# RX08-3-5-9.net
KiCad netlist of a schematic drawn in EAGLE
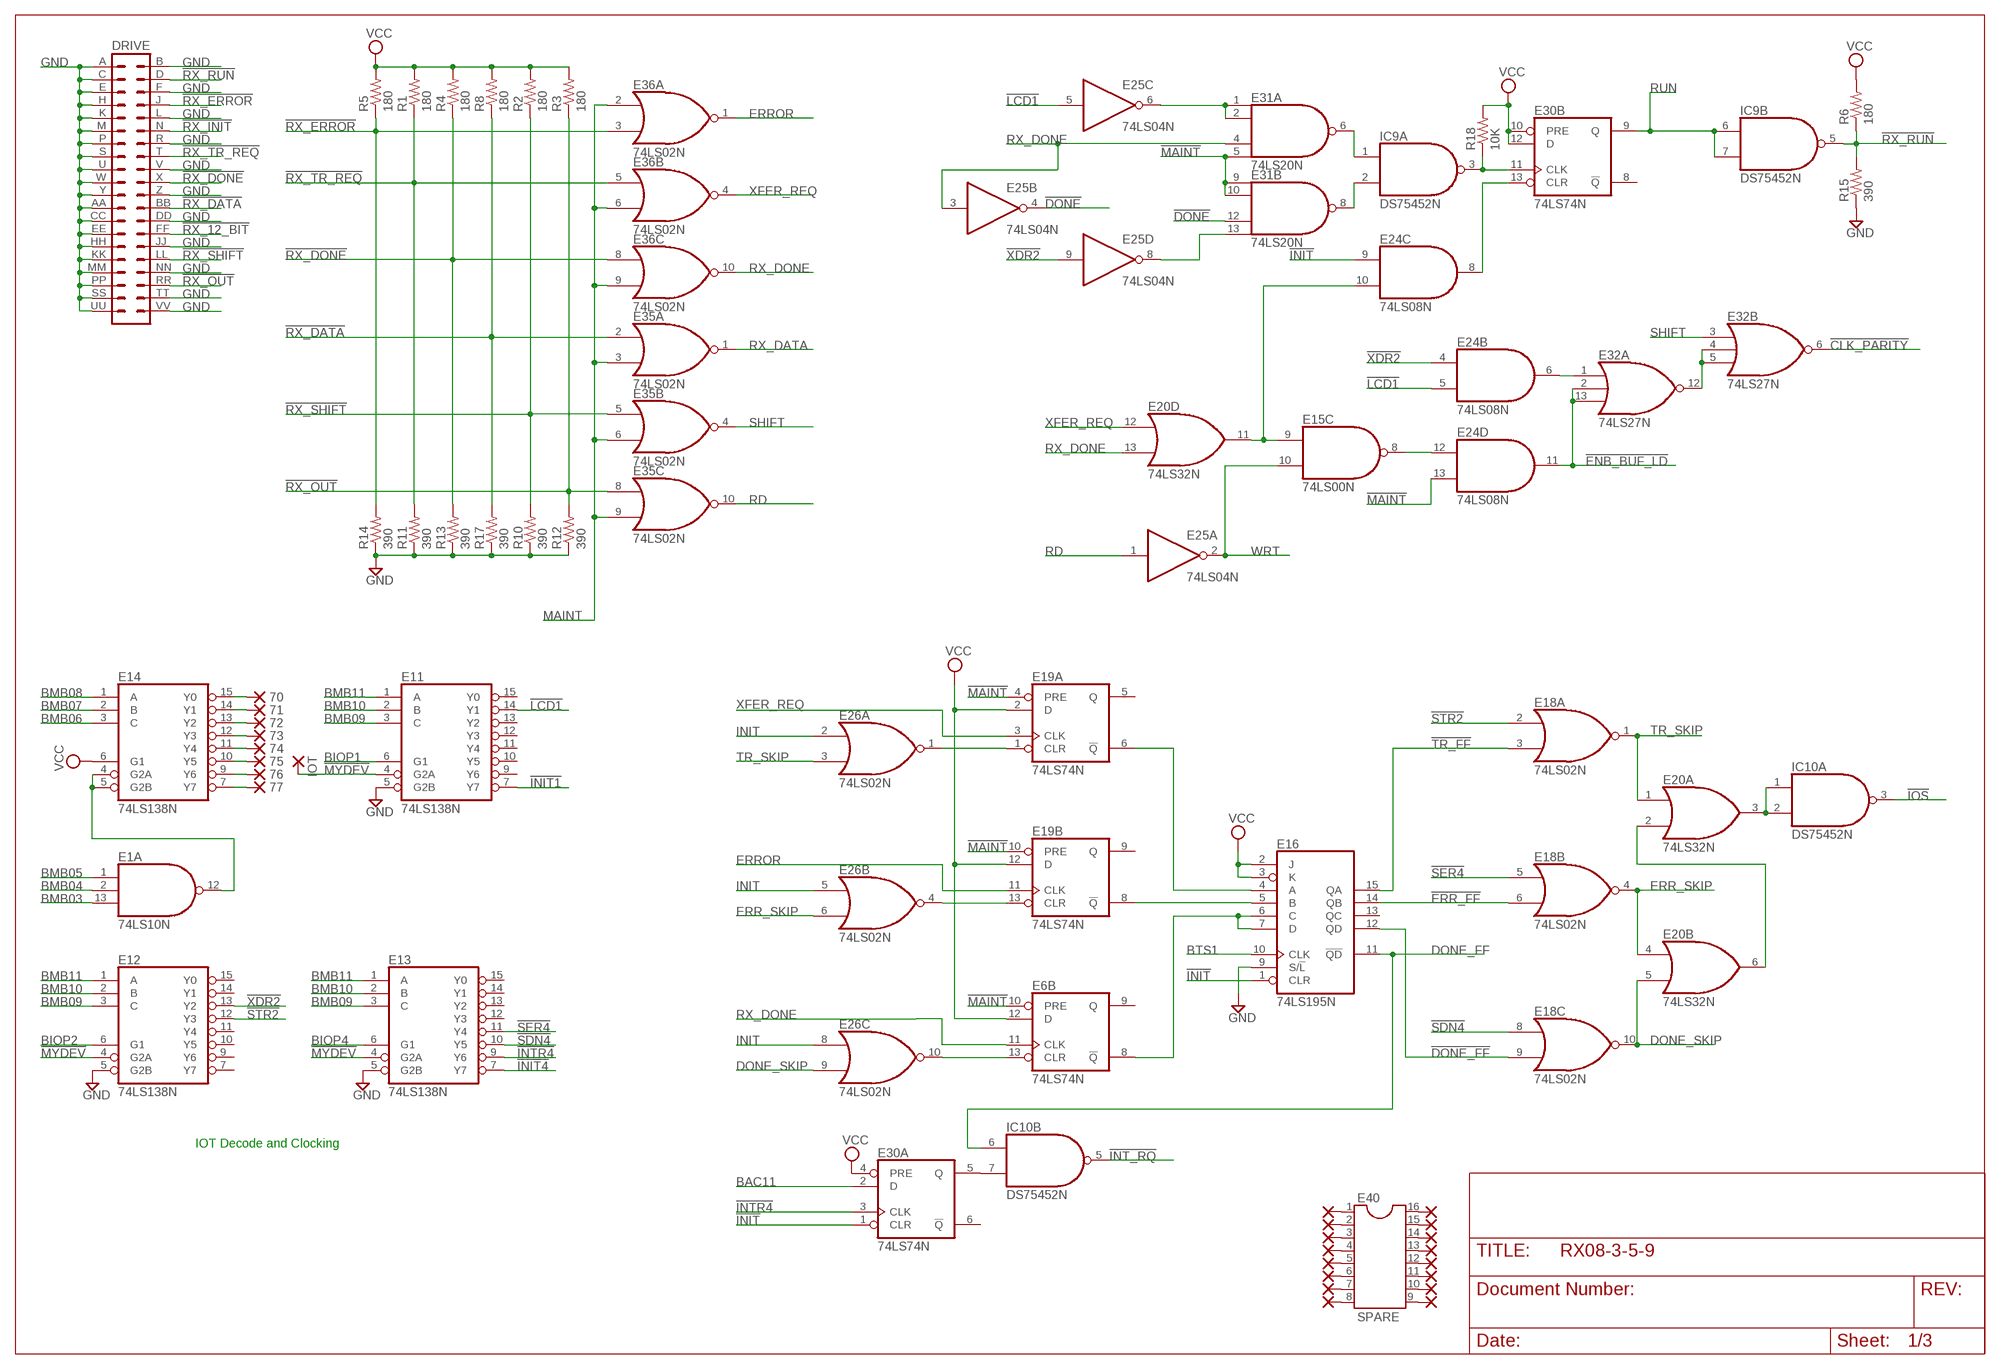
[diagram p0: schematic, sheet 1]
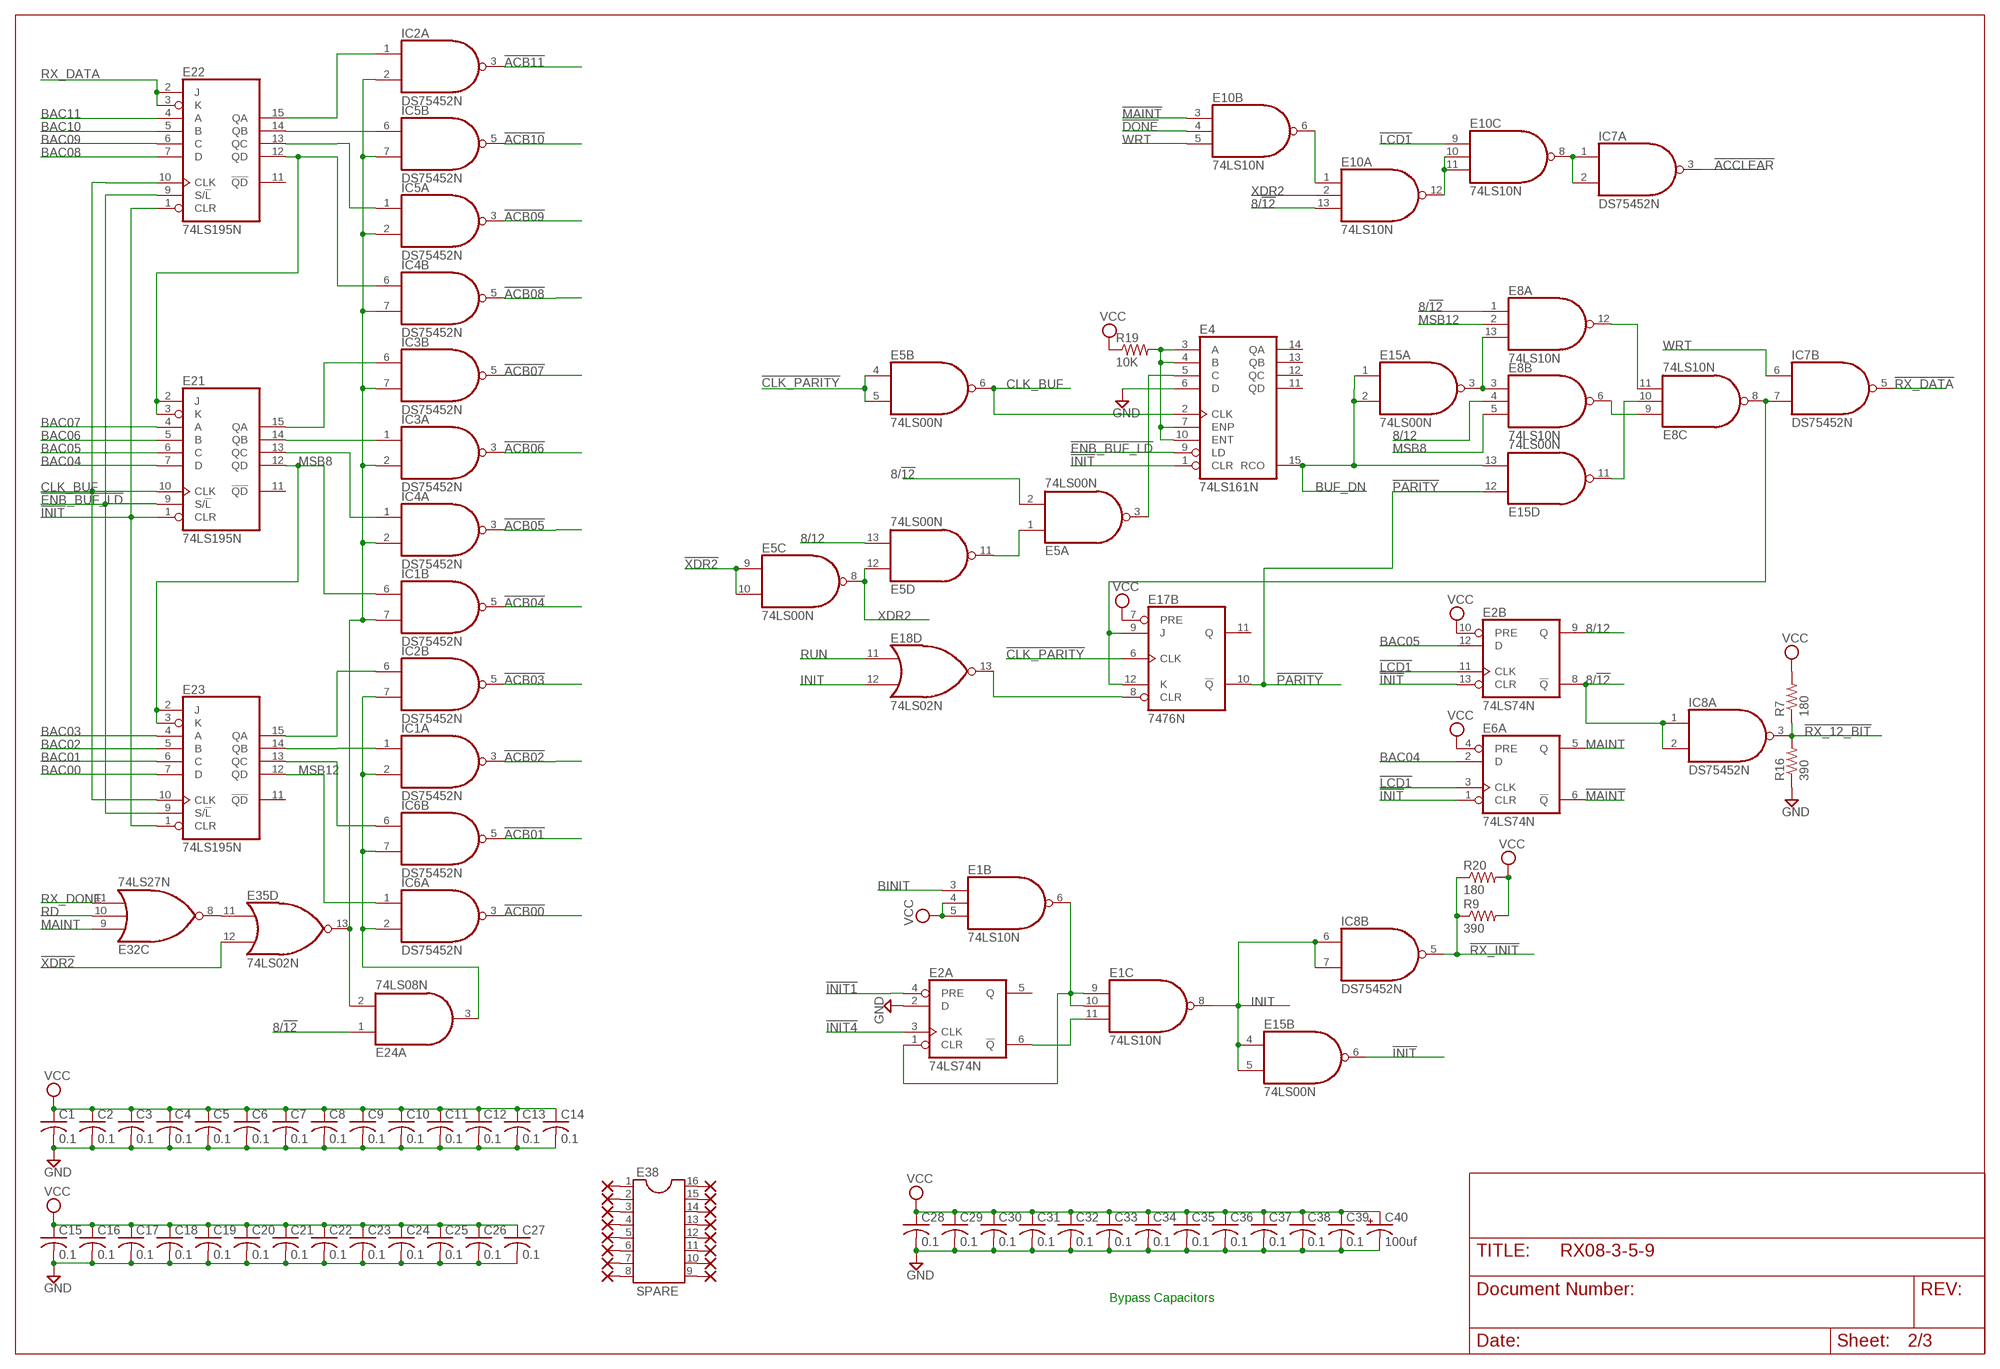
[diagram p1: schematic, sheet 2]
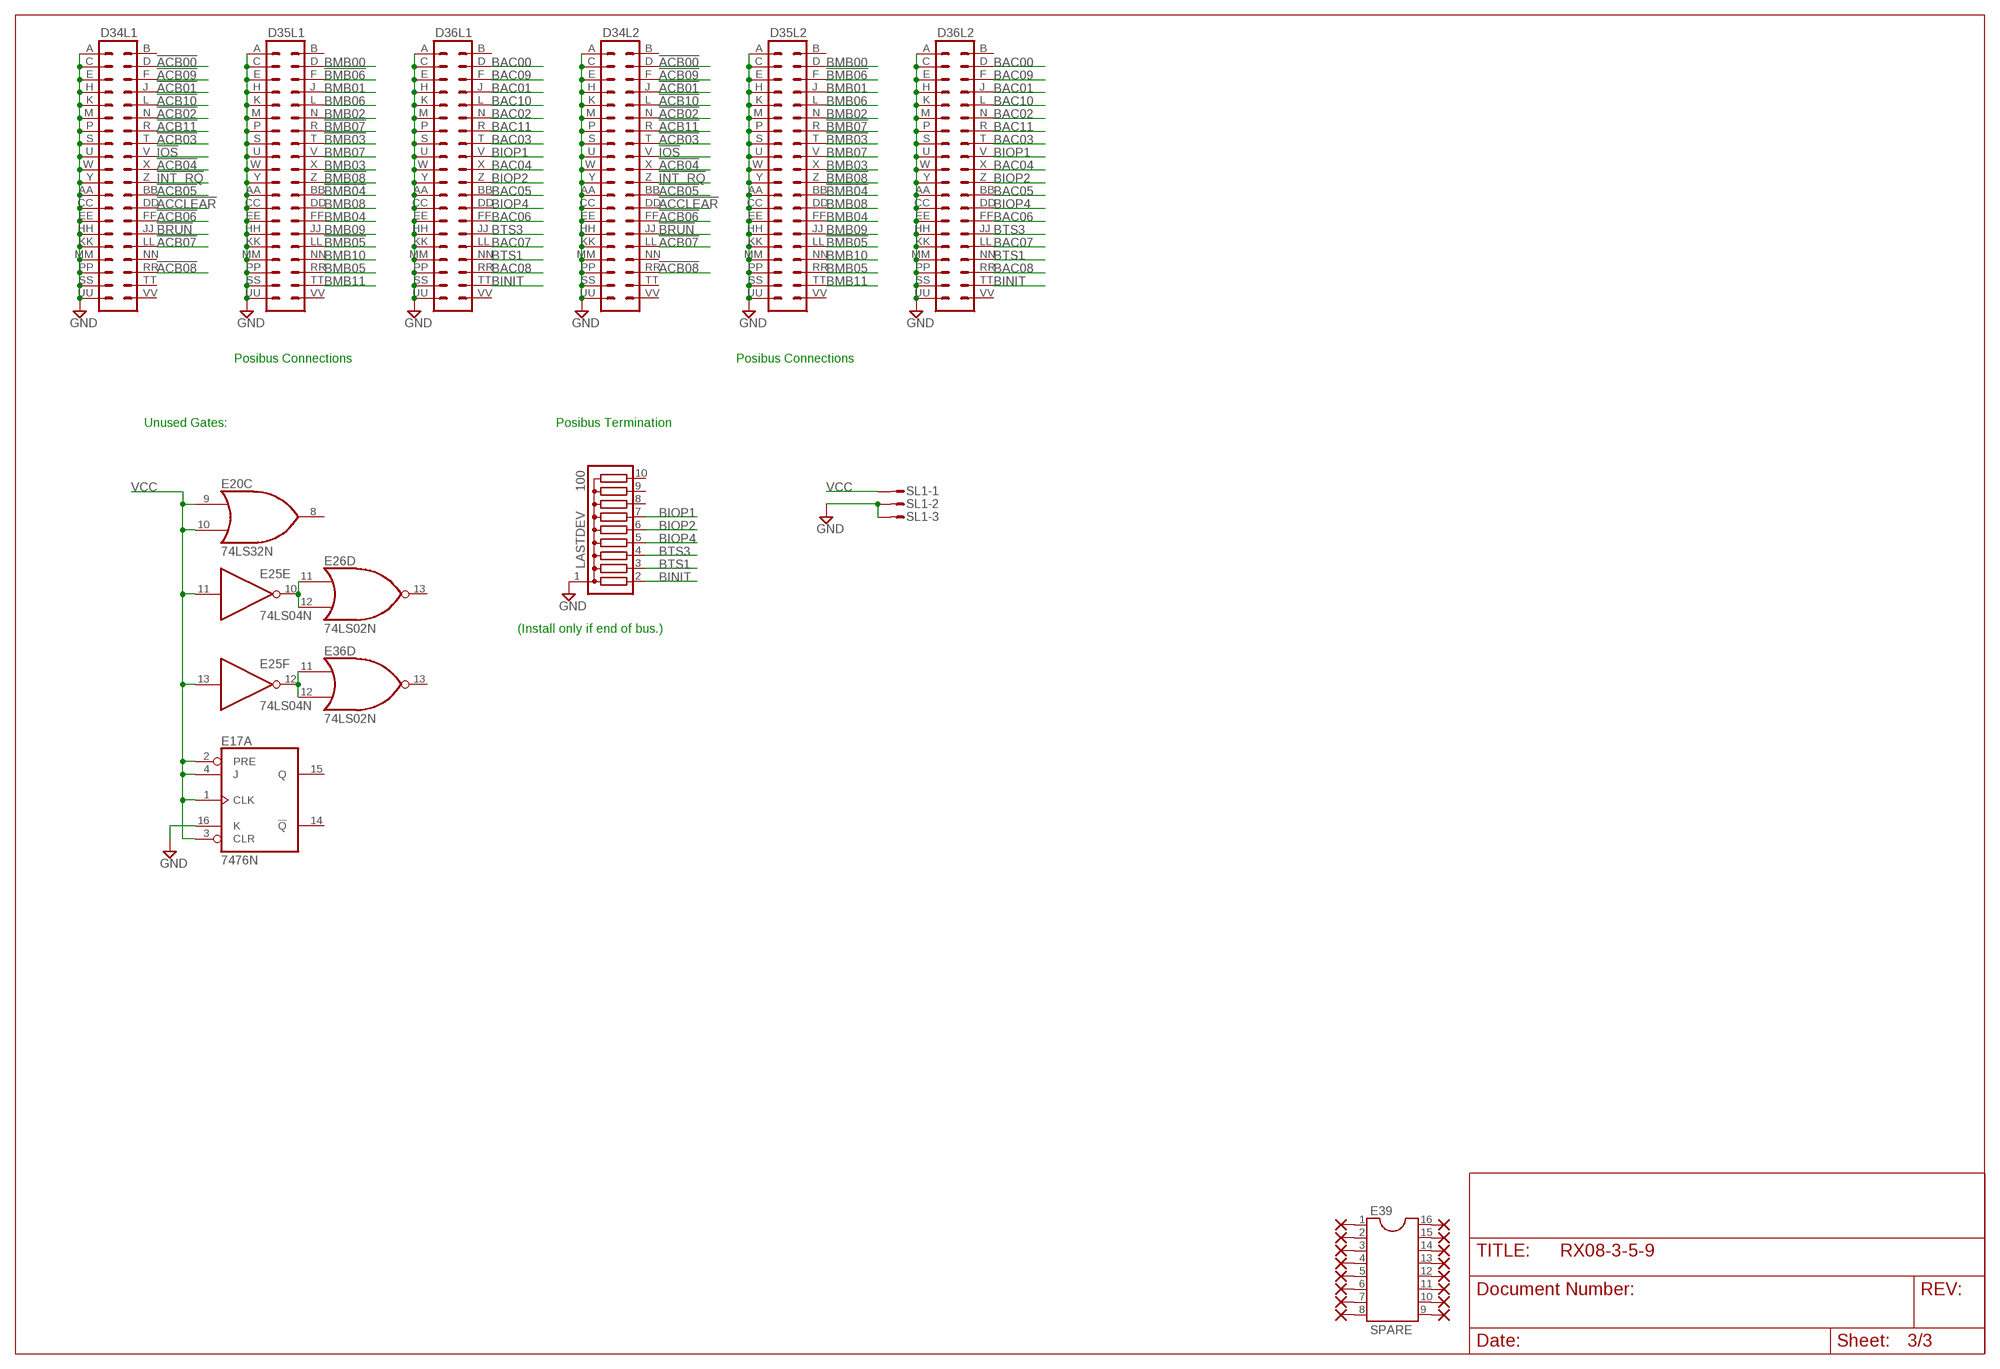
[diagram p2: schematic, sheet 3]

(export (version "E")
  (design (tool "Eeschema 10.0.6"))
  (components
    (comp (ref "C1")
      (value "0.1")
      (footprint "eagle-import:C050-025X075")
      (libsource (lib "eagle-import") (part "C-US050-025X075"))
    )
    (comp (ref "C2")
      (value "0.1")
      (footprint "eagle-import:C050-025X075")
      (libsource (lib "eagle-import") (part "C-US050-025X075"))
    )
    (comp (ref "C3")
      (value "0.1")
      (footprint "eagle-import:C050-025X075")
      (libsource (lib "eagle-import") (part "C-US050-025X075"))
    )
    (comp (ref "C4")
      (value "0.1")
      (footprint "eagle-import:C050-025X075")
      (libsource (lib "eagle-import") (part "C-US050-025X075"))
    )
    (comp (ref "C5")
      (value "0.1")
      (footprint "eagle-import:C050-025X075")
      (libsource (lib "eagle-import") (part "C-US050-025X075"))
    )
    (comp (ref "C6")
      (value "0.1")
      (footprint "eagle-import:C050-025X075")
      (libsource (lib "eagle-import") (part "C-US050-025X075"))
    )
    (comp (ref "C7")
      (value "0.1")
      (footprint "eagle-import:C050-025X075")
      (libsource (lib "eagle-import") (part "C-US050-025X075"))
    )
    (comp (ref "C8")
      (value "0.1")
      (footprint "eagle-import:C050-025X075")
      (libsource (lib "eagle-import") (part "C-US050-025X075"))
    )
    (comp (ref "C9")
      (value "0.1")
      (footprint "eagle-import:C050-025X075")
      (libsource (lib "eagle-import") (part "C-US050-025X075"))
    )
    (comp (ref "C10")
      (value "0.1")
      (footprint "eagle-import:C050-025X075")
      (libsource (lib "eagle-import") (part "C-US050-025X075"))
    )
    (comp (ref "C11")
      (value "0.1")
      (footprint "eagle-import:C050-025X075")
      (libsource (lib "eagle-import") (part "C-US050-025X075"))
    )
    (comp (ref "C12")
      (value "0.1")
      (footprint "eagle-import:C050-025X075")
      (libsource (lib "eagle-import") (part "C-US050-025X075"))
    )
    (comp (ref "C13")
      (value "0.1")
      (footprint "eagle-import:C050-025X075")
      (libsource (lib "eagle-import") (part "C-US050-025X075"))
    )
    (comp (ref "C14")
      (value "0.1")
      (footprint "eagle-import:C050-025X075")
      (libsource (lib "eagle-import") (part "C-US050-025X075"))
    )
    (comp (ref "C15")
      (value "0.1")
      (footprint "eagle-import:C050-025X075")
      (libsource (lib "eagle-import") (part "C-US050-025X075"))
    )
    (comp (ref "C16")
      (value "0.1")
      (footprint "eagle-import:C050-025X075")
      (libsource (lib "eagle-import") (part "C-US050-025X075"))
    )
    (comp (ref "C17")
      (value "0.1")
      (footprint "eagle-import:C050-025X075")
      (libsource (lib "eagle-import") (part "C-US050-025X075"))
    )
    (comp (ref "C18")
      (value "0.1")
      (footprint "eagle-import:C050-025X075")
      (libsource (lib "eagle-import") (part "C-US050-025X075"))
    )
    (comp (ref "C19")
      (value "0.1")
      (footprint "eagle-import:C050-025X075")
      (libsource (lib "eagle-import") (part "C-US050-025X075"))
    )
    (comp (ref "C20")
      (value "0.1")
      (footprint "eagle-import:C050-025X075")
      (libsource (lib "eagle-import") (part "C-US050-025X075"))
    )
    (comp (ref "C21")
      (value "0.1")
      (footprint "eagle-import:C050-025X075")
      (libsource (lib "eagle-import") (part "C-US050-025X075"))
    )
    (comp (ref "C22")
      (value "0.1")
      (footprint "eagle-import:C050-025X075")
      (libsource (lib "eagle-import") (part "C-US050-025X075"))
    )
    (comp (ref "C23")
      (value "0.1")
      (footprint "eagle-import:C050-025X075")
      (libsource (lib "eagle-import") (part "C-US050-025X075"))
    )
    (comp (ref "C24")
      (value "0.1")
      (footprint "eagle-import:C050-025X075")
      (libsource (lib "eagle-import") (part "C-US050-025X075"))
    )
    (comp (ref "C25")
      (value "0.1")
      (footprint "eagle-import:C050-025X075")
      (libsource (lib "eagle-import") (part "C-US050-025X075"))
    )
    (comp (ref "C26")
      (value "0.1")
      (footprint "eagle-import:C050-025X075")
      (libsource (lib "eagle-import") (part "C-US050-025X075"))
    )
    (comp (ref "C27")
      (value "0.1")
      (footprint "eagle-import:C050-025X075")
      (libsource (lib "eagle-import") (part "C-US050-025X075"))
    )
    (comp (ref "C28")
      (value "0.1")
      (footprint "eagle-import:C050-025X075")
      (libsource (lib "eagle-import") (part "C-US050-025X075"))
    )
    (comp (ref "C29")
      (value "0.1")
      (footprint "eagle-import:C050-025X075")
      (libsource (lib "eagle-import") (part "C-US050-025X075"))
    )
    (comp (ref "C30")
      (value "0.1")
      (footprint "eagle-import:C050-025X075")
      (libsource (lib "eagle-import") (part "C-US050-025X075"))
    )
    (comp (ref "C31")
      (value "0.1")
      (footprint "eagle-import:C050-025X075")
      (libsource (lib "eagle-import") (part "C-US050-025X075"))
    )
    (comp (ref "C32")
      (value "0.1")
      (footprint "eagle-import:C050-025X075")
      (libsource (lib "eagle-import") (part "C-US050-025X075"))
    )
    (comp (ref "C33")
      (value "0.1")
      (footprint "eagle-import:C050-025X075")
      (libsource (lib "eagle-import") (part "C-US050-025X075"))
    )
    (comp (ref "C34")
      (value "0.1")
      (footprint "eagle-import:C050-025X075")
      (libsource (lib "eagle-import") (part "C-US050-025X075"))
    )
    (comp (ref "C35")
      (value "0.1")
      (footprint "eagle-import:C050-025X075")
      (libsource (lib "eagle-import") (part "C-US050-025X075"))
    )
    (comp (ref "C36")
      (value "0.1")
      (footprint "eagle-import:C050-025X075")
      (libsource (lib "eagle-import") (part "C-US050-025X075"))
    )
    (comp (ref "C37")
      (value "0.1")
      (footprint "eagle-import:C050-025X075")
      (libsource (lib "eagle-import") (part "C-US050-025X075"))
    )
    (comp (ref "C38")
      (value "0.1")
      (footprint "eagle-import:C050-025X075")
      (libsource (lib "eagle-import") (part "C-US050-025X075"))
    )
    (comp (ref "C39")
      (value "0.1")
      (footprint "eagle-import:C050-025X075")
      (libsource (lib "eagle-import") (part "C-US050-025X075"))
    )
    (comp (ref "C40")
      (value "100uf")
      (footprint "eagle-import:E22-9")
      (libsource (lib "eagle-import") (part "CPOL-USE22-9AXIAL"))
    )
    (comp (ref "E1")
      (value "74LS10N")
      (footprint "eagle-import:DIL14")
      (libsource (lib "eagle-import") (part "7410NLS"))
    )
    (comp (ref "E2")
      (value "74LS74N")
      (footprint "eagle-import:DIL14")
      (libsource (lib "eagle-import") (part "7474NLS"))
    )
    (comp (ref "E4")
      (value "74LS161N")
      (footprint "eagle-import:DIL16")
      (libsource (lib "eagle-import") (part "74161NLS"))
    )
    (comp (ref "E5")
      (value "74LS00N")
      (footprint "eagle-import:DIL14")
      (libsource (lib "eagle-import") (part "7400NLS"))
    )
    (comp (ref "E6")
      (value "74LS74N")
      (footprint "eagle-import:DIL14")
      (libsource (lib "eagle-import") (part "7474NLS"))
    )
    (comp (ref "E8")
      (value "74LS10N")
      (footprint "eagle-import:DIL14")
      (libsource (lib "eagle-import") (part "7410NLS"))
    )
    (comp (ref "E10")
      (value "74LS10N")
      (footprint "eagle-import:DIL14")
      (libsource (lib "eagle-import") (part "7410NLS"))
    )
    (comp (ref "E15")
      (value "74LS00N")
      (footprint "eagle-import:DIL14")
      (libsource (lib "eagle-import") (part "7400NLS"))
    )
    (comp (ref "E17")
      (value "7476N")
      (footprint "eagle-import:DIL16")
      (libsource (lib "eagle-import") (part "7476N"))
    )
    (comp (ref "E18")
      (value "74LS02N")
      (footprint "eagle-import:DIL14")
      (libsource (lib "eagle-import") (part "7402NLS"))
    )
    (comp (ref "E21")
      (value "74LS195N")
      (footprint "eagle-import:DIL16")
      (libsource (lib "eagle-import") (part "74195NLS"))
    )
    (comp (ref "E22")
      (value "74LS195N")
      (footprint "eagle-import:DIL16")
      (libsource (lib "eagle-import") (part "74195NLS"))
    )
    (comp (ref "E23")
      (value "74LS195N")
      (footprint "eagle-import:DIL16")
      (libsource (lib "eagle-import") (part "74195NLS"))
    )
    (comp (ref "E24")
      (value "74LS08N")
      (footprint "eagle-import:DIL14")
      (libsource (lib "eagle-import") (part "7408NLS"))
    )
    (comp (ref "E32")
      (value "74LS27N")
      (footprint "eagle-import:DIL14")
      (libsource (lib "eagle-import") (part "7427NLS"))
    )
    (comp (ref "E35")
      (value "74LS02N")
      (footprint "eagle-import:DIL14")
      (libsource (lib "eagle-import") (part "7402NLS"))
    )
    (comp (ref "E38")
      (value "SPARE")
      (footprint "eagle-import:DIL16")
      (libsource (lib "eagle-import") (part "DIL16"))
    )
    (comp (ref "IC1")
      (value "DS75452N")
      (footprint "eagle-import:DIL08")
      (libsource (lib "eagle-import") (part "DS75452N"))
    )
    (comp (ref "IC2")
      (value "DS75452N")
      (footprint "eagle-import:DIL08")
      (libsource (lib "eagle-import") (part "DS75452N"))
    )
    (comp (ref "IC3")
      (value "DS75452N")
      (footprint "eagle-import:DIL08")
      (libsource (lib "eagle-import") (part "DS75452N"))
    )
    (comp (ref "IC4")
      (value "DS75452N")
      (footprint "eagle-import:DIL08")
      (libsource (lib "eagle-import") (part "DS75452N"))
    )
    (comp (ref "IC5")
      (value "DS75452N")
      (footprint "eagle-import:DIL08")
      (libsource (lib "eagle-import") (part "DS75452N"))
    )
    (comp (ref "IC6")
      (value "DS75452N")
      (footprint "eagle-import:DIL08")
      (libsource (lib "eagle-import") (part "DS75452N"))
    )
    (comp (ref "IC7")
      (value "DS75452N")
      (footprint "eagle-import:DIL08")
      (libsource (lib "eagle-import") (part "DS75452N"))
    )
    (comp (ref "IC8")
      (value "DS75452N")
      (footprint "eagle-import:DIL08")
      (libsource (lib "eagle-import") (part "DS75452N"))
    )
    (comp (ref "PAD10")
      (value "1,6/0,8")
      (footprint "eagle-import:1,6_0,8")
      (libsource (lib "eagle-import") (part "1,6/0,8"))
    )
    (comp (ref "PAD11")
      (value "1,6/0,8")
      (footprint "eagle-import:1,6_0,8")
      (libsource (lib "eagle-import") (part "1,6/0,8"))
    )
    (comp (ref "PAD12")
      (value "1,6/0,8")
      (footprint "eagle-import:1,6_0,8")
      (libsource (lib "eagle-import") (part "1,6/0,8"))
    )
    (comp (ref "PAD13")
      (value "1,6/0,8")
      (footprint "eagle-import:1,6_0,8")
      (libsource (lib "eagle-import") (part "1,6/0,8"))
    )
    (comp (ref "PAD14")
      (value "1,6/0,8")
      (footprint "eagle-import:1,6_0,8")
      (libsource (lib "eagle-import") (part "1,6/0,8"))
    )
    (comp (ref "PAD15")
      (value "1,6/0,8")
      (footprint "eagle-import:1,6_0,8")
      (libsource (lib "eagle-import") (part "1,6/0,8"))
    )
    (comp (ref "PAD16")
      (value "1,6/0,8")
      (footprint "eagle-import:1,6_0,8")
      (libsource (lib "eagle-import") (part "1,6/0,8"))
    )
    (comp (ref "PAD17")
      (value "1,6/0,8")
      (footprint "eagle-import:1,6_0,8")
      (libsource (lib "eagle-import") (part "1,6/0,8"))
    )
    (comp (ref "PAD20")
      (value "1,6/0,8")
      (footprint "eagle-import:1,6_0,8")
      (libsource (lib "eagle-import") (part "1,6/0,8"))
    )
    (comp (ref "PAD21")
      (value "1,6/0,8")
      (footprint "eagle-import:1,6_0,8")
      (libsource (lib "eagle-import") (part "1,6/0,8"))
    )
    (comp (ref "PAD22")
      (value "1,6/0,8")
      (footprint "eagle-import:1,6_0,8")
      (libsource (lib "eagle-import") (part "1,6/0,8"))
    )
    (comp (ref "PAD23")
      (value "1,6/0,8")
      (footprint "eagle-import:1,6_0,8")
      (libsource (lib "eagle-import") (part "1,6/0,8"))
    )
    (comp (ref "PAD24")
      (value "1,6/0,8")
      (footprint "eagle-import:1,6_0,8")
      (libsource (lib "eagle-import") (part "1,6/0,8"))
    )
    (comp (ref "PAD25")
      (value "1,6/0,8")
      (footprint "eagle-import:1,6_0,8")
      (libsource (lib "eagle-import") (part "1,6/0,8"))
    )
    (comp (ref "PAD26")
      (value "1,6/0,8")
      (footprint "eagle-import:1,6_0,8")
      (libsource (lib "eagle-import") (part "1,6/0,8"))
    )
    (comp (ref "PAD27")
      (value "1,6/0,8")
      (footprint "eagle-import:1,6_0,8")
      (libsource (lib "eagle-import") (part "1,6/0,8"))
    )
    (comp (ref "R7")
      (value "180")
      (footprint "eagle-import:0207_10")
      (libsource (lib "eagle-import") (part "R-US_0207/10"))
    )
    (comp (ref "R9")
      (value "390")
      (footprint "eagle-import:0207_10")
      (libsource (lib "eagle-import") (part "R-US_0207/10"))
    )
    (comp (ref "R16")
      (value "390")
      (footprint "eagle-import:0207_10")
      (libsource (lib "eagle-import") (part "R-US_0207/10"))
    )
    (comp (ref "R19")
      (value "10K")
      (footprint "eagle-import:0207_10")
      (libsource (lib "eagle-import") (part "R-US_0207/10"))
    )
    (comp (ref "R20")
      (value "180")
      (footprint "eagle-import:0207_10")
      (libsource (lib "eagle-import") (part "R-US_0207/10"))
    )
    (comp (ref "D34L1")
      (value "DEC40PINV")
      (footprint "eagle-import:DEC40PINV")
      (libsource (lib "eagle-import") (part "DEC40PINV"))
    )
    (comp (ref "D34L2")
      (value "DEC40PINV")
      (footprint "eagle-import:DEC40PINV")
      (libsource (lib "eagle-import") (part "DEC40PINV"))
    )
    (comp (ref "D35L1")
      (value "DEC40PINV")
      (footprint "eagle-import:DEC40PINV")
      (libsource (lib "eagle-import") (part "DEC40PINV"))
    )
    (comp (ref "D35L2")
      (value "DEC40PINV")
      (footprint "eagle-import:DEC40PINV")
      (libsource (lib "eagle-import") (part "DEC40PINV"))
    )
    (comp (ref "D36L1")
      (value "DEC40PINV")
      (footprint "eagle-import:DEC40PINV")
      (libsource (lib "eagle-import") (part "DEC40PINV"))
    )
    (comp (ref "D36L2")
      (value "DEC40PINV")
      (footprint "eagle-import:DEC40PINV")
      (libsource (lib "eagle-import") (part "DEC40PINV"))
    )
    (comp (ref "E20")
      (value "74LS32N")
      (footprint "eagle-import:DIL14")
      (libsource (lib "eagle-import") (part "7432NLS"))
    )
    (comp (ref "E25")
      (value "74LS04N")
      (footprint "eagle-import:DIL14")
      (libsource (lib "eagle-import") (part "7404NLS"))
    )
    (comp (ref "E26")
      (value "74LS02N")
      (footprint "eagle-import:DIL14")
      (libsource (lib "eagle-import") (part "7402NLS"))
    )
    (comp (ref "E36")
      (value "74LS02N")
      (footprint "eagle-import:DIL14")
      (libsource (lib "eagle-import") (part "7402NLS"))
    )
    (comp (ref "E39")
      (value "SPARE")
      (footprint "eagle-import:DIL16")
      (libsource (lib "eagle-import") (part "DIL16"))
    )
    (comp (ref "LASTDEV")
      (value "100")
      (footprint "eagle-import:SIL10")
      (libsource (lib "eagle-import") (part "G09R"))
    )
    (comp (ref "PAD42")
      (value "1,6/0,8")
      (footprint "eagle-import:1,6_0,8")
      (libsource (lib "eagle-import") (part "1,6/0,8"))
    )
    (comp (ref "PAD43")
      (value "1,6/0,8")
      (footprint "eagle-import:1,6_0,8")
      (libsource (lib "eagle-import") (part "1,6/0,8"))
    )
    (comp (ref "PAD44")
      (value "1,6/0,8")
      (footprint "eagle-import:1,6_0,8")
      (libsource (lib "eagle-import") (part "1,6/0,8"))
    )
    (comp (ref "PAD45")
      (value "1,6/0,8")
      (footprint "eagle-import:1,6_0,8")
      (libsource (lib "eagle-import") (part "1,6/0,8"))
    )
    (comp (ref "PAD46")
      (value "1,6/0,8")
      (footprint "eagle-import:1,6_0,8")
      (libsource (lib "eagle-import") (part "1,6/0,8"))
    )
    (comp (ref "PAD47")
      (value "1,6/0,8")
      (footprint "eagle-import:1,6_0,8")
      (libsource (lib "eagle-import") (part "1,6/0,8"))
    )
    (comp (ref "PAD48")
      (value "1,6/0,8")
      (footprint "eagle-import:1,6_0,8")
      (libsource (lib "eagle-import") (part "1,6/0,8"))
    )
    (comp (ref "PAD49")
      (value "1,6/0,8")
      (footprint "eagle-import:1,6_0,8")
      (libsource (lib "eagle-import") (part "1,6/0,8"))
    )
    (comp (ref "PAD50")
      (value "1,6/0,8")
      (footprint "eagle-import:1,6_0,8")
      (libsource (lib "eagle-import") (part "1,6/0,8"))
    )
    (comp (ref "PAD51")
      (value "1,6/0,8")
      (footprint "eagle-import:1,6_0,8")
      (libsource (lib "eagle-import") (part "1,6/0,8"))
    )
    (comp (ref "PAD52")
      (value "1,6/0,8")
      (footprint "eagle-import:1,6_0,8")
      (libsource (lib "eagle-import") (part "1,6/0,8"))
    )
    (comp (ref "PAD53")
      (value "1,6/0,8")
      (footprint "eagle-import:1,6_0,8")
      (libsource (lib "eagle-import") (part "1,6/0,8"))
    )
    (comp (ref "PAD54")
      (value "1,6/0,8")
      (footprint "eagle-import:1,6_0,8")
      (libsource (lib "eagle-import") (part "1,6/0,8"))
    )
    (comp (ref "PAD55")
      (value "1,6/0,8")
      (footprint "eagle-import:1,6_0,8")
      (libsource (lib "eagle-import") (part "1,6/0,8"))
    )
    (comp (ref "PAD56")
      (value "1,6/0,8")
      (footprint "eagle-import:1,6_0,8")
      (libsource (lib "eagle-import") (part "1,6/0,8"))
    )
    (comp (ref "PAD57")
      (value "1,6/0,8")
      (footprint "eagle-import:1,6_0,8")
      (libsource (lib "eagle-import") (part "1,6/0,8"))
    )
    (comp (ref "SL1")
      (value "MA04S")
      (footprint "eagle-import:04PA")
      (libsource (lib "eagle-import") (part "MA04S"))
    )
    (comp (ref "70")
      (value "1,6/0,8")
      (footprint "eagle-import:1,6_0,8")
      (libsource (lib "eagle-import") (part "1,6/0,8"))
    )
    (comp (ref "71")
      (value "1,6/0,8")
      (footprint "eagle-import:1,6_0,8")
      (libsource (lib "eagle-import") (part "1,6/0,8"))
    )
    (comp (ref "72")
      (value "1,6/0,8")
      (footprint "eagle-import:1,6_0,8")
      (libsource (lib "eagle-import") (part "1,6/0,8"))
    )
    (comp (ref "73")
      (value "1,6/0,8")
      (footprint "eagle-import:1,6_0,8")
      (libsource (lib "eagle-import") (part "1,6/0,8"))
    )
    (comp (ref "74")
      (value "1,6/0,8")
      (footprint "eagle-import:1,6_0,8")
      (libsource (lib "eagle-import") (part "1,6/0,8"))
    )
    (comp (ref "75")
      (value "1,6/0,8")
      (footprint "eagle-import:1,6_0,8")
      (libsource (lib "eagle-import") (part "1,6/0,8"))
    )
    (comp (ref "76")
      (value "1,6/0,8")
      (footprint "eagle-import:1,6_0,8")
      (libsource (lib "eagle-import") (part "1,6/0,8"))
    )
    (comp (ref "77")
      (value "1,6/0,8")
      (footprint "eagle-import:1,6_0,8")
      (libsource (lib "eagle-import") (part "1,6/0,8"))
    )
    (comp (ref "DRIVE")
      (value "DEC40PINV")
      (footprint "eagle-import:DEC40PINV")
      (libsource (lib "eagle-import") (part "DEC40PINV"))
    )
    (comp (ref "E11")
      (value "74LS138N")
      (footprint "eagle-import:DIL16")
      (libsource (lib "eagle-import") (part "74138NLS"))
    )
    (comp (ref "E12")
      (value "74LS138N")
      (footprint "eagle-import:DIL16")
      (libsource (lib "eagle-import") (part "74138NLS"))
    )
    (comp (ref "E13")
      (value "74LS138N")
      (footprint "eagle-import:DIL16")
      (libsource (lib "eagle-import") (part "74138NLS"))
    )
    (comp (ref "E14")
      (value "74LS138N")
      (footprint "eagle-import:DIL16")
      (libsource (lib "eagle-import") (part "74138NLS"))
    )
    (comp (ref "E16")
      (value "74LS195N")
      (footprint "eagle-import:DIL16")
      (libsource (lib "eagle-import") (part "74195NLS"))
    )
    (comp (ref "E19")
      (value "74LS74N")
      (footprint "eagle-import:DIL14")
      (libsource (lib "eagle-import") (part "7474NLS"))
    )
    (comp (ref "E30")
      (value "74LS74N")
      (footprint "eagle-import:DIL14")
      (libsource (lib "eagle-import") (part "7474NLS"))
    )
    (comp (ref "E31")
      (value "74LS20N")
      (footprint "eagle-import:DIL14")
      (libsource (lib "eagle-import") (part "7420NLS"))
    )
    (comp (ref "E40")
      (value "SPARE")
      (footprint "eagle-import:DIL16")
      (libsource (lib "eagle-import") (part "DIL16"))
    )
    (comp (ref "IC9")
      (value "DS75452N")
      (footprint "eagle-import:DIL08")
      (libsource (lib "eagle-import") (part "DS75452N"))
    )
    (comp (ref "IC10")
      (value "DS75452N")
      (footprint "eagle-import:DIL08")
      (libsource (lib "eagle-import") (part "DS75452N"))
    )
    (comp (ref "IOT")
      (value "1,6/0,8")
      (footprint "eagle-import:1,6_0,8")
      (libsource (lib "eagle-import") (part "1,6/0,8"))
    )
    (comp (ref "PAD18")
      (value "1,6/0,8")
      (footprint "eagle-import:1,6_0,8")
      (libsource (lib "eagle-import") (part "1,6/0,8"))
    )
    (comp (ref "PAD19")
      (value "1,6/0,8")
      (footprint "eagle-import:1,6_0,8")
      (libsource (lib "eagle-import") (part "1,6/0,8"))
    )
    (comp (ref "PAD28")
      (value "1,6/0,8")
      (footprint "eagle-import:1,6_0,8")
      (libsource (lib "eagle-import") (part "1,6/0,8"))
    )
    (comp (ref "PAD29")
      (value "1,6/0,8")
      (footprint "eagle-import:1,6_0,8")
      (libsource (lib "eagle-import") (part "1,6/0,8"))
    )
    (comp (ref "PAD30")
      (value "1,6/0,8")
      (footprint "eagle-import:1,6_0,8")
      (libsource (lib "eagle-import") (part "1,6/0,8"))
    )
    (comp (ref "PAD31")
      (value "1,6/0,8")
      (footprint "eagle-import:1,6_0,8")
      (libsource (lib "eagle-import") (part "1,6/0,8"))
    )
    (comp (ref "PAD32")
      (value "1,6/0,8")
      (footprint "eagle-import:1,6_0,8")
      (libsource (lib "eagle-import") (part "1,6/0,8"))
    )
    (comp (ref "PAD33")
      (value "1,6/0,8")
      (footprint "eagle-import:1,6_0,8")
      (libsource (lib "eagle-import") (part "1,6/0,8"))
    )
    (comp (ref "PAD34")
      (value "1,6/0,8")
      (footprint "eagle-import:1,6_0,8")
      (libsource (lib "eagle-import") (part "1,6/0,8"))
    )
    (comp (ref "PAD35")
      (value "1,6/0,8")
      (footprint "eagle-import:1,6_0,8")
      (libsource (lib "eagle-import") (part "1,6/0,8"))
    )
    (comp (ref "PAD36")
      (value "1,6/0,8")
      (footprint "eagle-import:1,6_0,8")
      (libsource (lib "eagle-import") (part "1,6/0,8"))
    )
    (comp (ref "PAD37")
      (value "1,6/0,8")
      (footprint "eagle-import:1,6_0,8")
      (libsource (lib "eagle-import") (part "1,6/0,8"))
    )
    (comp (ref "PAD38")
      (value "1,6/0,8")
      (footprint "eagle-import:1,6_0,8")
      (libsource (lib "eagle-import") (part "1,6/0,8"))
    )
    (comp (ref "PAD39")
      (value "1,6/0,8")
      (footprint "eagle-import:1,6_0,8")
      (libsource (lib "eagle-import") (part "1,6/0,8"))
    )
    (comp (ref "PAD40")
      (value "1,6/0,8")
      (footprint "eagle-import:1,6_0,8")
      (libsource (lib "eagle-import") (part "1,6/0,8"))
    )
    (comp (ref "PAD41")
      (value "1,6/0,8")
      (footprint "eagle-import:1,6_0,8")
      (libsource (lib "eagle-import") (part "1,6/0,8"))
    )
    (comp (ref "R1")
      (value "180")
      (footprint "eagle-import:0207_10")
      (libsource (lib "eagle-import") (part "R-US_0207/10"))
    )
    (comp (ref "R2")
      (value "180")
      (footprint "eagle-import:0207_10")
      (libsource (lib "eagle-import") (part "R-US_0207/10"))
    )
    (comp (ref "R3")
      (value "180")
      (footprint "eagle-import:0207_10")
      (libsource (lib "eagle-import") (part "R-US_0207/10"))
    )
    (comp (ref "R4")
      (value "180")
      (footprint "eagle-import:0207_10")
      (libsource (lib "eagle-import") (part "R-US_0207/10"))
    )
    (comp (ref "R5")
      (value "180")
      (footprint "eagle-import:0207_10")
      (libsource (lib "eagle-import") (part "R-US_0207/10"))
    )
    (comp (ref "R6")
      (value "180")
      (footprint "eagle-import:0207_10")
      (libsource (lib "eagle-import") (part "R-US_0207/10"))
    )
    (comp (ref "R8")
      (value "180")
      (footprint "eagle-import:0207_10")
      (libsource (lib "eagle-import") (part "R-US_0207/10"))
    )
    (comp (ref "R10")
      (value "390")
      (footprint "eagle-import:0207_10")
      (libsource (lib "eagle-import") (part "R-US_0207/10"))
    )
    (comp (ref "R11")
      (value "390")
      (footprint "eagle-import:0207_10")
      (libsource (lib "eagle-import") (part "R-US_0207/10"))
    )
    (comp (ref "R12")
      (value "390")
      (footprint "eagle-import:0207_10")
      (libsource (lib "eagle-import") (part "R-US_0207/10"))
    )
    (comp (ref "R13")
      (value "390")
      (footprint "eagle-import:0207_10")
      (libsource (lib "eagle-import") (part "R-US_0207/10"))
    )
    (comp (ref "R14")
      (value "390")
      (footprint "eagle-import:0207_10")
      (libsource (lib "eagle-import") (part "R-US_0207/10"))
    )
    (comp (ref "R15")
      (value "390")
      (footprint "eagle-import:0207_10")
      (libsource (lib "eagle-import") (part "R-US_0207/10"))
    )
    (comp (ref "R17")
      (value "390")
      (footprint "eagle-import:0207_10")
      (libsource (lib "eagle-import") (part "R-US_0207/10"))
    )
    (comp (ref "R18")
      (value "10K")
      (footprint "eagle-import:0207_10")
      (libsource (lib "eagle-import") (part "R-US_0207/10"))
    )
  )
  (nets
    (net (code "1") (name "8{slash}12") (class "Default")
      (node (ref "E2") (pin "9") (pinfunction "Q_9") (pintype "output"))
      (node (ref "E5") (pin "13") (pinfunction "I1_13") (pintype "input"))
      (node (ref "E8") (pin "4") (pinfunction "I1_4") (pintype "input"))
    )
    (net (code "2") (name "8{slash}~{12}") (class "Default")
      (node (ref "E10") (pin "13") (pinfunction "I2_13") (pintype "input"))
      (node (ref "E2") (pin "8") (pinfunction "~{Q}_8") (pintype "output"))
      (node (ref "E24") (pin "1") (pinfunction "I0_1") (pintype "input"))
      (node (ref "E5") (pin "2") (pinfunction "I1_2") (pintype "input"))
      (node (ref "E8") (pin "1") (pinfunction "I0_1") (pintype "input"))
      (node (ref "IC8") (pin "1") (pinfunction "I0_1") (pintype "input"))
      (node (ref "IC8") (pin "2") (pinfunction "I1_2") (pintype "input"))
    )
    (net (code "3") (name "BAC00") (class "Default")
      (node (ref "D36L1") (pin "D") (pinfunction "4_D") (pintype "bidirectional"))
      (node (ref "D36L2") (pin "D") (pinfunction "4_D") (pintype "bidirectional"))
      (node (ref "E23") (pin "7") (pinfunction "D_7") (pintype "input"))
    )
    (net (code "4") (name "BAC01") (class "Default")
      (node (ref "D36L1") (pin "J") (pinfunction "8_J") (pintype "bidirectional"))
      (node (ref "D36L2") (pin "J") (pinfunction "8_J") (pintype "bidirectional"))
      (node (ref "E23") (pin "6") (pinfunction "C_6") (pintype "input"))
    )
    (net (code "5") (name "BAC02") (class "Default")
      (node (ref "D36L1") (pin "N") (pinfunction "12_N") (pintype "bidirectional"))
      (node (ref "D36L2") (pin "N") (pinfunction "12_N") (pintype "bidirectional"))
      (node (ref "E23") (pin "5") (pinfunction "B_5") (pintype "input"))
    )
    (net (code "6") (name "BAC03") (class "Default")
      (node (ref "D36L1") (pin "T") (pinfunction "16_T") (pintype "bidirectional"))
      (node (ref "D36L2") (pin "T") (pinfunction "16_T") (pintype "bidirectional"))
      (node (ref "E23") (pin "4") (pinfunction "A_4") (pintype "input"))
    )
    (net (code "7") (name "BAC04") (class "Default")
      (node (ref "D36L1") (pin "X") (pinfunction "20_X") (pintype "bidirectional"))
      (node (ref "D36L2") (pin "X") (pinfunction "20_X") (pintype "bidirectional"))
      (node (ref "E21") (pin "7") (pinfunction "D_7") (pintype "input"))
      (node (ref "E6") (pin "2") (pinfunction "D_2") (pintype "input"))
    )
    (net (code "8") (name "BAC05") (class "Default")
      (node (ref "D36L1") (pin "BB") (pinfunction "24_BB") (pintype "bidirectional"))
      (node (ref "D36L2") (pin "BB") (pinfunction "24_BB") (pintype "bidirectional"))
      (node (ref "E2") (pin "12") (pinfunction "D_12") (pintype "input"))
      (node (ref "E21") (pin "6") (pinfunction "C_6") (pintype "input"))
    )
    (net (code "9") (name "BAC06") (class "Default")
      (node (ref "D36L1") (pin "FF") (pinfunction "28_FF") (pintype "bidirectional"))
      (node (ref "D36L2") (pin "FF") (pinfunction "28_FF") (pintype "bidirectional"))
      (node (ref "E21") (pin "5") (pinfunction "B_5") (pintype "input"))
    )
    (net (code "10") (name "BAC07") (class "Default")
      (node (ref "D36L1") (pin "LL") (pinfunction "32_LL") (pintype "bidirectional"))
      (node (ref "D36L2") (pin "LL") (pinfunction "32_LL") (pintype "bidirectional"))
      (node (ref "E21") (pin "4") (pinfunction "A_4") (pintype "input"))
    )
    (net (code "11") (name "BAC08") (class "Default")
      (node (ref "D36L1") (pin "RR") (pinfunction "36_RR") (pintype "bidirectional"))
      (node (ref "D36L2") (pin "RR") (pinfunction "36_RR") (pintype "bidirectional"))
      (node (ref "E22") (pin "7") (pinfunction "D_7") (pintype "input"))
    )
    (net (code "12") (name "BAC09") (class "Default")
      (node (ref "D36L1") (pin "F") (pinfunction "6_F") (pintype "bidirectional"))
      (node (ref "D36L2") (pin "F") (pinfunction "6_F") (pintype "bidirectional"))
      (node (ref "E22") (pin "6") (pinfunction "C_6") (pintype "input"))
    )
    (net (code "13") (name "BAC10") (class "Default")
      (node (ref "D36L1") (pin "L") (pinfunction "10_L") (pintype "bidirectional"))
      (node (ref "D36L2") (pin "L") (pinfunction "10_L") (pintype "bidirectional"))
      (node (ref "E22") (pin "5") (pinfunction "B_5") (pintype "input"))
    )
    (net (code "14") (name "BAC11") (class "Default")
      (node (ref "D36L1") (pin "R") (pinfunction "14_R") (pintype "bidirectional"))
      (node (ref "D36L2") (pin "R") (pinfunction "14_R") (pintype "bidirectional"))
      (node (ref "E22") (pin "4") (pinfunction "A_4") (pintype "input"))
      (node (ref "E30") (pin "2") (pinfunction "D_2") (pintype "input"))
    )
    (net (code "15") (name "BINIT") (class "Default")
      (node (ref "D36L1") (pin "TT") (pinfunction "38_TT") (pintype "bidirectional"))
      (node (ref "D36L2") (pin "TT") (pinfunction "38_TT") (pintype "bidirectional"))
      (node (ref "E1") (pin "3") (pinfunction "I0_3") (pintype "input"))
      (node (ref "LASTDEV") (pin "2") (pinfunction "2_2") (pintype "passive"))
    )
    (net (code "16") (name "BIOP1") (class "Default")
      (node (ref "D36L1") (pin "V") (pinfunction "18_V") (pintype "bidirectional"))
      (node (ref "D36L2") (pin "V") (pinfunction "18_V") (pintype "bidirectional"))
      (node (ref "E11") (pin "6") (pinfunction "G1_6") (pintype "input"))
      (node (ref "LASTDEV") (pin "7") (pinfunction "7_7") (pintype "passive"))
    )
    (net (code "17") (name "BIOP2") (class "Default")
      (node (ref "D36L1") (pin "Z") (pinfunction "22_Z") (pintype "bidirectional"))
      (node (ref "D36L2") (pin "Z") (pinfunction "22_Z") (pintype "bidirectional"))
      (node (ref "E12") (pin "6") (pinfunction "G1_6") (pintype "input"))
      (node (ref "LASTDEV") (pin "6") (pinfunction "6_6") (pintype "passive"))
    )
    (net (code "18") (name "BIOP4") (class "Default")
      (node (ref "D36L1") (pin "DD") (pinfunction "26_DD") (pintype "bidirectional"))
      (node (ref "D36L2") (pin "DD") (pinfunction "26_DD") (pintype "bidirectional"))
      (node (ref "E13") (pin "6") (pinfunction "G1_6") (pintype "input"))
      (node (ref "LASTDEV") (pin "5") (pinfunction "5_5") (pintype "passive"))
    )
    (net (code "19") (name "BMB00") (class "Default")
      (node (ref "D35L1") (pin "D") (pinfunction "4_D") (pintype "bidirectional"))
      (node (ref "D35L2") (pin "D") (pinfunction "4_D") (pintype "bidirectional"))
    )
    (net (code "20") (name "BMB01") (class "Default")
      (node (ref "D35L1") (pin "J") (pinfunction "8_J") (pintype "bidirectional"))
      (node (ref "D35L2") (pin "J") (pinfunction "8_J") (pintype "bidirectional"))
    )
    (net (code "21") (name "BMB02") (class "Default")
      (node (ref "D35L1") (pin "N") (pinfunction "12_N") (pintype "bidirectional"))
      (node (ref "D35L2") (pin "N") (pinfunction "12_N") (pintype "bidirectional"))
    )
    (net (code "22") (name "BMB03") (class "Default")
      (node (ref "D35L1") (pin "X") (pinfunction "20_X") (pintype "bidirectional"))
      (node (ref "D35L2") (pin "X") (pinfunction "20_X") (pintype "bidirectional"))
      (node (ref "E1") (pin "13") (pinfunction "I2_13") (pintype "input"))
    )
    (net (code "23") (name "BMB04") (class "Default")
      (node (ref "D35L1") (pin "FF") (pinfunction "28_FF") (pintype "bidirectional"))
      (node (ref "D35L2") (pin "FF") (pinfunction "28_FF") (pintype "bidirectional"))
      (node (ref "E1") (pin "2") (pinfunction "I1_2") (pintype "input"))
    )
    (net (code "24") (name "BMB05") (class "Default")
      (node (ref "D35L1") (pin "RR") (pinfunction "36_RR") (pintype "bidirectional"))
      (node (ref "D35L2") (pin "RR") (pinfunction "36_RR") (pintype "bidirectional"))
      (node (ref "E1") (pin "1") (pinfunction "I0_1") (pintype "input"))
    )
    (net (code "25") (name "BMB06") (class "Default")
      (node (ref "D35L1") (pin "L") (pinfunction "10_L") (pintype "bidirectional"))
      (node (ref "D35L2") (pin "L") (pinfunction "10_L") (pintype "bidirectional"))
      (node (ref "E14") (pin "3") (pinfunction "C_3") (pintype "input"))
    )
    (net (code "26") (name "BMB07") (class "Default")
      (node (ref "D35L1") (pin "V") (pinfunction "18_V") (pintype "bidirectional"))
      (node (ref "D35L2") (pin "V") (pinfunction "18_V") (pintype "bidirectional"))
      (node (ref "E14") (pin "2") (pinfunction "B_2") (pintype "input"))
    )
    (net (code "27") (name "BMB08") (class "Default")
      (node (ref "D35L1") (pin "DD") (pinfunction "26_DD") (pintype "bidirectional"))
      (node (ref "D35L2") (pin "DD") (pinfunction "26_DD") (pintype "bidirectional"))
      (node (ref "E14") (pin "1") (pinfunction "A_1") (pintype "input"))
    )
    (net (code "28") (name "BMB09") (class "Default")
      (node (ref "D35L1") (pin "JJ") (pinfunction "30_JJ") (pintype "bidirectional"))
      (node (ref "D35L2") (pin "JJ") (pinfunction "30_JJ") (pintype "bidirectional"))
      (node (ref "E11") (pin "3") (pinfunction "C_3") (pintype "input"))
      (node (ref "E12") (pin "3") (pinfunction "C_3") (pintype "input"))
      (node (ref "E13") (pin "3") (pinfunction "C_3") (pintype "input"))
    )
    (net (code "29") (name "BMB10") (class "Default")
      (node (ref "D35L1") (pin "NN") (pinfunction "34_NN") (pintype "bidirectional"))
      (node (ref "D35L2") (pin "NN") (pinfunction "34_NN") (pintype "bidirectional"))
      (node (ref "E11") (pin "2") (pinfunction "B_2") (pintype "input"))
      (node (ref "E12") (pin "2") (pinfunction "B_2") (pintype "input"))
      (node (ref "E13") (pin "2") (pinfunction "B_2") (pintype "input"))
    )
    (net (code "30") (name "BMB11") (class "Default")
      (node (ref "D35L1") (pin "TT") (pinfunction "38_TT") (pintype "bidirectional"))
      (node (ref "D35L2") (pin "TT") (pinfunction "38_TT") (pintype "bidirectional"))
      (node (ref "E11") (pin "1") (pinfunction "A_1") (pintype "input"))
      (node (ref "E12") (pin "1") (pinfunction "A_1") (pintype "input"))
      (node (ref "E13") (pin "1") (pinfunction "A_1") (pintype "input"))
    )
    (net (code "31") (name "BTS1") (class "Default")
      (node (ref "D36L1") (pin "NN") (pinfunction "34_NN") (pintype "bidirectional"))
      (node (ref "D36L2") (pin "NN") (pinfunction "34_NN") (pintype "bidirectional"))
      (node (ref "E16") (pin "10") (pinfunction "CLK_10") (pintype "input"))
      (node (ref "LASTDEV") (pin "3") (pinfunction "3_3") (pintype "passive"))
    )
    (net (code "32") (name "BTS3") (class "Default")
      (node (ref "D36L1") (pin "JJ") (pinfunction "30_JJ") (pintype "bidirectional"))
      (node (ref "D36L2") (pin "JJ") (pinfunction "30_JJ") (pintype "bidirectional"))
      (node (ref "LASTDEV") (pin "4") (pinfunction "4_4") (pintype "passive"))
    )
    (net (code "33") (name "BUF_DN") (class "Default")
      (node (ref "E15") (pin "1") (pinfunction "I0_1") (pintype "input"))
      (node (ref "E15") (pin "13") (pinfunction "I1_13") (pintype "input"))
      (node (ref "E15") (pin "2") (pinfunction "I1_2") (pintype "input"))
      (node (ref "E4") (pin "15") (pinfunction "RCO_15") (pintype "output"))
    )
    (net (code "34") (name "CLK_BUF") (class "Default")
      (node (ref "E21") (pin "10") (pinfunction "CLK_10") (pintype "input"))
      (node (ref "E22") (pin "10") (pinfunction "CLK_10") (pintype "input"))
      (node (ref "E23") (pin "10") (pinfunction "CLK_10") (pintype "input"))
      (node (ref "E4") (pin "2") (pinfunction "CLK_2") (pintype "input"))
      (node (ref "E5") (pin "6") (pinfunction "O_6") (pintype "output"))
    )
    (net (code "35") (name "DONE_FF") (class "Default")
      (node (ref "E16") (pin "11") (pinfunction "~{QD}_11") (pintype "output"))
      (node (ref "IC10") (pin "6") (pinfunction "I0_6") (pintype "input"))
    )
    (net (code "36") (name "DONE_SKIP") (class "Default")
      (node (ref "E18") (pin "10") (pinfunction "O_10") (pintype "output"))
      (node (ref "E20") (pin "5") (pinfunction "I1_5") (pintype "input"))
      (node (ref "E26") (pin "9") (pinfunction "I1_9") (pintype "input"))
    )
    (net (code "37") (name "ERROR") (class "Default")
      (node (ref "E19") (pin "11") (pinfunction "CLK_11") (pintype "input"))
      (node (ref "E36") (pin "1") (pinfunction "O_1") (pintype "output"))
    )
    (net (code "38") (name "ERR_SKIP") (class "Default")
      (node (ref "E18") (pin "4") (pinfunction "O_4") (pintype "output"))
      (node (ref "E20") (pin "4") (pinfunction "I0_4") (pintype "input"))
      (node (ref "E26") (pin "6") (pinfunction "I1_6") (pintype "input"))
    )
    (net (code "39") (name "GND") (class "Default")
      (node (ref "C1") (pin "2") (pinfunction "2_2") (pintype "passive"))
      (node (ref "C10") (pin "2") (pinfunction "2_2") (pintype "passive"))
      (node (ref "C11") (pin "2") (pinfunction "2_2") (pintype "passive"))
      (node (ref "C12") (pin "2") (pinfunction "2_2") (pintype "passive"))
      (node (ref "C13") (pin "2") (pinfunction "2_2") (pintype "passive"))
      (node (ref "C14") (pin "2") (pinfunction "2_2") (pintype "passive"))
      (node (ref "C15") (pin "2") (pinfunction "2_2") (pintype "passive"))
      (node (ref "C16") (pin "2") (pinfunction "2_2") (pintype "passive"))
      (node (ref "C17") (pin "2") (pinfunction "2_2") (pintype "passive"))
      (node (ref "C18") (pin "2") (pinfunction "2_2") (pintype "passive"))
      (node (ref "C19") (pin "2") (pinfunction "2_2") (pintype "passive"))
      (node (ref "C2") (pin "2") (pinfunction "2_2") (pintype "passive"))
      (node (ref "C20") (pin "2") (pinfunction "2_2") (pintype "passive"))
      (node (ref "C21") (pin "2") (pinfunction "2_2") (pintype "passive"))
      (node (ref "C22") (pin "2") (pinfunction "2_2") (pintype "passive"))
      (node (ref "C23") (pin "2") (pinfunction "2_2") (pintype "passive"))
      (node (ref "C24") (pin "2") (pinfunction "2_2") (pintype "passive"))
      (node (ref "C25") (pin "2") (pinfunction "2_2") (pintype "passive"))
      (node (ref "C26") (pin "2") (pinfunction "2_2") (pintype "passive"))
      (node (ref "C27") (pin "2") (pinfunction "2_2") (pintype "passive"))
      (node (ref "C28") (pin "2") (pinfunction "2_2") (pintype "passive"))
      (node (ref "C29") (pin "2") (pinfunction "2_2") (pintype "passive"))
      (node (ref "C3") (pin "2") (pinfunction "2_2") (pintype "passive"))
      (node (ref "C30") (pin "2") (pinfunction "2_2") (pintype "passive"))
      (node (ref "C31") (pin "2") (pinfunction "2_2") (pintype "passive"))
      (node (ref "C32") (pin "2") (pinfunction "2_2") (pintype "passive"))
      (node (ref "C33") (pin "2") (pinfunction "2_2") (pintype "passive"))
      (node (ref "C34") (pin "2") (pinfunction "2_2") (pintype "passive"))
      (node (ref "C35") (pin "2") (pinfunction "2_2") (pintype "passive"))
      (node (ref "C36") (pin "2") (pinfunction "2_2") (pintype "passive"))
      (node (ref "C37") (pin "2") (pinfunction "2_2") (pintype "passive"))
      (node (ref "C38") (pin "2") (pinfunction "2_2") (pintype "passive"))
      (node (ref "C39") (pin "2") (pinfunction "2_2") (pintype "passive"))
      (node (ref "C4") (pin "2") (pinfunction "2_2") (pintype "passive"))
      (node (ref "C40") (pin "-") (pinfunction "-_-") (pintype "passive"))
      (node (ref "C5") (pin "2") (pinfunction "2_2") (pintype "passive"))
      (node (ref "C6") (pin "2") (pinfunction "2_2") (pintype "passive"))
      (node (ref "C7") (pin "2") (pinfunction "2_2") (pintype "passive"))
      (node (ref "C8") (pin "2") (pinfunction "2_2") (pintype "passive"))
      (node (ref "C9") (pin "2") (pinfunction "2_2") (pintype "passive"))
      (node (ref "D34L1") (pin "A") (pinfunction "1_A") (pintype "bidirectional"))
      (node (ref "D34L1") (pin "AA") (pinfunction "23_AA") (pintype "bidirectional"))
      (node (ref "D34L1") (pin "C") (pinfunction "3_C") (pintype "bidirectional"))
      (node (ref "D34L1") (pin "CC") (pinfunction "25_CC") (pintype "bidirectional"))
      (node (ref "D34L1") (pin "E") (pinfunction "5_E") (pintype "bidirectional"))
      (node (ref "D34L1") (pin "EE") (pinfunction "27_EE") (pintype "bidirectional"))
      (node (ref "D34L1") (pin "H") (pinfunction "7_H") (pintype "bidirectional"))
      (node (ref "D34L1") (pin "HH") (pinfunction "29_HH") (pintype "bidirectional"))
      (node (ref "D34L1") (pin "K") (pinfunction "9_K") (pintype "bidirectional"))
      (node (ref "D34L1") (pin "KK") (pinfunction "31_KK") (pintype "bidirectional"))
      (node (ref "D34L1") (pin "M") (pinfunction "11_M") (pintype "bidirectional"))
      (node (ref "D34L1") (pin "MM") (pinfunction "33_MM") (pintype "bidirectional"))
      (node (ref "D34L1") (pin "P") (pinfunction "13_P") (pintype "bidirectional"))
      (node (ref "D34L1") (pin "PP") (pinfunction "35_PP") (pintype "bidirectional"))
      (node (ref "D34L1") (pin "S") (pinfunction "15_S") (pintype "bidirectional"))
      (node (ref "D34L1") (pin "SS") (pinfunction "37_SS") (pintype "bidirectional"))
      (node (ref "D34L1") (pin "U") (pinfunction "17_U") (pintype "bidirectional"))
      (node (ref "D34L1") (pin "UU") (pinfunction "39_UU") (pintype "bidirectional"))
      (node (ref "D34L1") (pin "W") (pinfunction "19_W") (pintype "bidirectional"))
      (node (ref "D34L1") (pin "Y") (pinfunction "21_Y") (pintype "bidirectional"))
      (node (ref "D34L2") (pin "A") (pinfunction "1_A") (pintype "bidirectional"))
      (node (ref "D34L2") (pin "AA") (pinfunction "23_AA") (pintype "bidirectional"))
      (node (ref "D34L2") (pin "C") (pinfunction "3_C") (pintype "bidirectional"))
      (node (ref "D34L2") (pin "CC") (pinfunction "25_CC") (pintype "bidirectional"))
      (node (ref "D34L2") (pin "E") (pinfunction "5_E") (pintype "bidirectional"))
      (node (ref "D34L2") (pin "EE") (pinfunction "27_EE") (pintype "bidirectional"))
      (node (ref "D34L2") (pin "H") (pinfunction "7_H") (pintype "bidirectional"))
      (node (ref "D34L2") (pin "HH") (pinfunction "29_HH") (pintype "bidirectional"))
      (node (ref "D34L2") (pin "K") (pinfunction "9_K") (pintype "bidirectional"))
      (node (ref "D34L2") (pin "KK") (pinfunction "31_KK") (pintype "bidirectional"))
      (node (ref "D34L2") (pin "M") (pinfunction "11_M") (pintype "bidirectional"))
      (node (ref "D34L2") (pin "MM") (pinfunction "33_MM") (pintype "bidirectional"))
      (node (ref "D34L2") (pin "P") (pinfunction "13_P") (pintype "bidirectional"))
      (node (ref "D34L2") (pin "PP") (pinfunction "35_PP") (pintype "bidirectional"))
      (node (ref "D34L2") (pin "S") (pinfunction "15_S") (pintype "bidirectional"))
      (node (ref "D34L2") (pin "SS") (pinfunction "37_SS") (pintype "bidirectional"))
      (node (ref "D34L2") (pin "U") (pinfunction "17_U") (pintype "bidirectional"))
      (node (ref "D34L2") (pin "UU") (pinfunction "39_UU") (pintype "bidirectional"))
      (node (ref "D34L2") (pin "W") (pinfunction "19_W") (pintype "bidirectional"))
      (node (ref "D34L2") (pin "Y") (pinfunction "21_Y") (pintype "bidirectional"))
      (node (ref "D35L1") (pin "A") (pinfunction "1_A") (pintype "bidirectional"))
      (node (ref "D35L1") (pin "AA") (pinfunction "23_AA") (pintype "bidirectional"))
      (node (ref "D35L1") (pin "C") (pinfunction "3_C") (pintype "bidirectional"))
      (node (ref "D35L1") (pin "CC") (pinfunction "25_CC") (pintype "bidirectional"))
      (node (ref "D35L1") (pin "E") (pinfunction "5_E") (pintype "bidirectional"))
      (node (ref "D35L1") (pin "EE") (pinfunction "27_EE") (pintype "bidirectional"))
      (node (ref "D35L1") (pin "H") (pinfunction "7_H") (pintype "bidirectional"))
      (node (ref "D35L1") (pin "HH") (pinfunction "29_HH") (pintype "bidirectional"))
      (node (ref "D35L1") (pin "K") (pinfunction "9_K") (pintype "bidirectional"))
      (node (ref "D35L1") (pin "KK") (pinfunction "31_KK") (pintype "bidirectional"))
      (node (ref "D35L1") (pin "M") (pinfunction "11_M") (pintype "bidirectional"))
      (node (ref "D35L1") (pin "MM") (pinfunction "33_MM") (pintype "bidirectional"))
      (node (ref "D35L1") (pin "P") (pinfunction "13_P") (pintype "bidirectional"))
      (node (ref "D35L1") (pin "PP") (pinfunction "35_PP") (pintype "bidirectional"))
      (node (ref "D35L1") (pin "S") (pinfunction "15_S") (pintype "bidirectional"))
      (node (ref "D35L1") (pin "SS") (pinfunction "37_SS") (pintype "bidirectional"))
      (node (ref "D35L1") (pin "U") (pinfunction "17_U") (pintype "bidirectional"))
      (node (ref "D35L1") (pin "UU") (pinfunction "39_UU") (pintype "bidirectional"))
      (node (ref "D35L1") (pin "W") (pinfunction "19_W") (pintype "bidirectional"))
      (node (ref "D35L1") (pin "Y") (pinfunction "21_Y") (pintype "bidirectional"))
      (node (ref "D35L2") (pin "A") (pinfunction "1_A") (pintype "bidirectional"))
      (node (ref "D35L2") (pin "AA") (pinfunction "23_AA") (pintype "bidirectional"))
      (node (ref "D35L2") (pin "C") (pinfunction "3_C") (pintype "bidirectional"))
      (node (ref "D35L2") (pin "CC") (pinfunction "25_CC") (pintype "bidirectional"))
      (node (ref "D35L2") (pin "E") (pinfunction "5_E") (pintype "bidirectional"))
      (node (ref "D35L2") (pin "EE") (pinfunction "27_EE") (pintype "bidirectional"))
      (node (ref "D35L2") (pin "H") (pinfunction "7_H") (pintype "bidirectional"))
      (node (ref "D35L2") (pin "HH") (pinfunction "29_HH") (pintype "bidirectional"))
      (node (ref "D35L2") (pin "K") (pinfunction "9_K") (pintype "bidirectional"))
      (node (ref "D35L2") (pin "KK") (pinfunction "31_KK") (pintype "bidirectional"))
      (node (ref "D35L2") (pin "M") (pinfunction "11_M") (pintype "bidirectional"))
      (node (ref "D35L2") (pin "MM") (pinfunction "33_MM") (pintype "bidirectional"))
      (node (ref "D35L2") (pin "P") (pinfunction "13_P") (pintype "bidirectional"))
      (node (ref "D35L2") (pin "PP") (pinfunction "35_PP") (pintype "bidirectional"))
      (node (ref "D35L2") (pin "S") (pinfunction "15_S") (pintype "bidirectional"))
      (node (ref "D35L2") (pin "SS") (pinfunction "37_SS") (pintype "bidirectional"))
      (node (ref "D35L2") (pin "U") (pinfunction "17_U") (pintype "bidirectional"))
      (node (ref "D35L2") (pin "UU") (pinfunction "39_UU") (pintype "bidirectional"))
      (node (ref "D35L2") (pin "W") (pinfunction "19_W") (pintype "bidirectional"))
      (node (ref "D35L2") (pin "Y") (pinfunction "21_Y") (pintype "bidirectional"))
      (node (ref "D36L1") (pin "A") (pinfunction "1_A") (pintype "bidirectional"))
      (node (ref "D36L1") (pin "AA") (pinfunction "23_AA") (pintype "bidirectional"))
      (node (ref "D36L1") (pin "C") (pinfunction "3_C") (pintype "bidirectional"))
      (node (ref "D36L1") (pin "CC") (pinfunction "25_CC") (pintype "bidirectional"))
      (node (ref "D36L1") (pin "E") (pinfunction "5_E") (pintype "bidirectional"))
      (node (ref "D36L1") (pin "EE") (pinfunction "27_EE") (pintype "bidirectional"))
      (node (ref "D36L1") (pin "H") (pinfunction "7_H") (pintype "bidirectional"))
      (node (ref "D36L1") (pin "HH") (pinfunction "29_HH") (pintype "bidirectional"))
      (node (ref "D36L1") (pin "K") (pinfunction "9_K") (pintype "bidirectional"))
      (node (ref "D36L1") (pin "KK") (pinfunction "31_KK") (pintype "bidirectional"))
      (node (ref "D36L1") (pin "M") (pinfunction "11_M") (pintype "bidirectional"))
      (node (ref "D36L1") (pin "MM") (pinfunction "33_MM") (pintype "bidirectional"))
      (node (ref "D36L1") (pin "P") (pinfunction "13_P") (pintype "bidirectional"))
      (node (ref "D36L1") (pin "PP") (pinfunction "35_PP") (pintype "bidirectional"))
      (node (ref "D36L1") (pin "S") (pinfunction "15_S") (pintype "bidirectional"))
      (node (ref "D36L1") (pin "SS") (pinfunction "37_SS") (pintype "bidirectional"))
      (node (ref "D36L1") (pin "U") (pinfunction "17_U") (pintype "bidirectional"))
      (node (ref "D36L1") (pin "UU") (pinfunction "39_UU") (pintype "bidirectional"))
      (node (ref "D36L1") (pin "W") (pinfunction "19_W") (pintype "bidirectional"))
      (node (ref "D36L1") (pin "Y") (pinfunction "21_Y") (pintype "bidirectional"))
      (node (ref "D36L2") (pin "A") (pinfunction "1_A") (pintype "bidirectional"))
      (node (ref "D36L2") (pin "AA") (pinfunction "23_AA") (pintype "bidirectional"))
      (node (ref "D36L2") (pin "C") (pinfunction "3_C") (pintype "bidirectional"))
      (node (ref "D36L2") (pin "CC") (pinfunction "25_CC") (pintype "bidirectional"))
      (node (ref "D36L2") (pin "E") (pinfunction "5_E") (pintype "bidirectional"))
      (node (ref "D36L2") (pin "EE") (pinfunction "27_EE") (pintype "bidirectional"))
      (node (ref "D36L2") (pin "H") (pinfunction "7_H") (pintype "bidirectional"))
      (node (ref "D36L2") (pin "HH") (pinfunction "29_HH") (pintype "bidirectional"))
      (node (ref "D36L2") (pin "K") (pinfunction "9_K") (pintype "bidirectional"))
      (node (ref "D36L2") (pin "KK") (pinfunction "31_KK") (pintype "bidirectional"))
      (node (ref "D36L2") (pin "M") (pinfunction "11_M") (pintype "bidirectional"))
      (node (ref "D36L2") (pin "MM") (pinfunction "33_MM") (pintype "bidirectional"))
      (node (ref "D36L2") (pin "P") (pinfunction "13_P") (pintype "bidirectional"))
      (node (ref "D36L2") (pin "PP") (pinfunction "35_PP") (pintype "bidirectional"))
      (node (ref "D36L2") (pin "S") (pinfunction "15_S") (pintype "bidirectional"))
      (node (ref "D36L2") (pin "SS") (pinfunction "37_SS") (pintype "bidirectional"))
      (node (ref "D36L2") (pin "U") (pinfunction "17_U") (pintype "bidirectional"))
      (node (ref "D36L2") (pin "UU") (pinfunction "39_UU") (pintype "bidirectional"))
      (node (ref "D36L2") (pin "W") (pinfunction "19_W") (pintype "bidirectional"))
      (node (ref "D36L2") (pin "Y") (pinfunction "21_Y") (pintype "bidirectional"))
      (node (ref "DRIVE") (pin "A") (pinfunction "1_A") (pintype "bidirectional"))
      (node (ref "DRIVE") (pin "AA") (pinfunction "23_AA") (pintype "bidirectional"))
      (node (ref "DRIVE") (pin "B") (pinfunction "2_B") (pintype "bidirectional"))
      (node (ref "DRIVE") (pin "C") (pinfunction "3_C") (pintype "bidirectional"))
      (node (ref "DRIVE") (pin "CC") (pinfunction "25_CC") (pintype "bidirectional"))
      (node (ref "DRIVE") (pin "DD") (pinfunction "26_DD") (pintype "bidirectional"))
      (node (ref "DRIVE") (pin "E") (pinfunction "5_E") (pintype "bidirectional"))
      (node (ref "DRIVE") (pin "EE") (pinfunction "27_EE") (pintype "bidirectional"))
      (node (ref "DRIVE") (pin "F") (pinfunction "6_F") (pintype "bidirectional"))
      (node (ref "DRIVE") (pin "H") (pinfunction "7_H") (pintype "bidirectional"))
      (node (ref "DRIVE") (pin "HH") (pinfunction "29_HH") (pintype "bidirectional"))
      (node (ref "DRIVE") (pin "JJ") (pinfunction "30_JJ") (pintype "bidirectional"))
      (node (ref "DRIVE") (pin "K") (pinfunction "9_K") (pintype "bidirectional"))
      (node (ref "DRIVE") (pin "KK") (pinfunction "31_KK") (pintype "bidirectional"))
      (node (ref "DRIVE") (pin "L") (pinfunction "10_L") (pintype "bidirectional"))
      (node (ref "DRIVE") (pin "M") (pinfunction "11_M") (pintype "bidirectional"))
      (node (ref "DRIVE") (pin "MM") (pinfunction "33_MM") (pintype "bidirectional"))
      (node (ref "DRIVE") (pin "NN") (pinfunction "34_NN") (pintype "bidirectional"))
      (node (ref "DRIVE") (pin "P") (pinfunction "13_P") (pintype "bidirectional"))
      (node (ref "DRIVE") (pin "PP") (pinfunction "35_PP") (pintype "bidirectional"))
      (node (ref "DRIVE") (pin "R") (pinfunction "14_R") (pintype "bidirectional"))
      (node (ref "DRIVE") (pin "S") (pinfunction "15_S") (pintype "bidirectional"))
      (node (ref "DRIVE") (pin "SS") (pinfunction "37_SS") (pintype "bidirectional"))
      (node (ref "DRIVE") (pin "TT") (pinfunction "38_TT") (pintype "bidirectional"))
      (node (ref "DRIVE") (pin "U") (pinfunction "17_U") (pintype "bidirectional"))
      (node (ref "DRIVE") (pin "UU") (pinfunction "39_UU") (pintype "bidirectional"))
      (node (ref "DRIVE") (pin "V") (pinfunction "18_V") (pintype "bidirectional"))
      (node (ref "DRIVE") (pin "VV") (pinfunction "40_VV") (pintype "bidirectional"))
      (node (ref "DRIVE") (pin "W") (pinfunction "19_W") (pintype "bidirectional"))
      (node (ref "DRIVE") (pin "Y") (pinfunction "21_Y") (pintype "bidirectional"))
      (node (ref "DRIVE") (pin "Z") (pinfunction "22_Z") (pintype "bidirectional"))
      (node (ref "E11") (pin "5") (pinfunction "G2B_5") (pintype "input"))
      (node (ref "E12") (pin "5") (pinfunction "G2B_5") (pintype "input"))
      (node (ref "E13") (pin "5") (pinfunction "G2B_5") (pintype "input"))
      (node (ref "E16") (pin "9") (pinfunction "S/~{L}_9") (pintype "input"))
      (node (ref "E17") (pin "16") (pinfunction "K_16") (pintype "input"))
      (node (ref "E2") (pin "2") (pinfunction "D_2") (pintype "input"))
      (node (ref "E4") (pin "6") (pinfunction "D_6") (pintype "input"))
      (node (ref "LASTDEV") (pin "1") (pinfunction "1_1") (pintype "passive"))
      (node (ref "R10") (pin "1") (pinfunction "1_1") (pintype "passive"))
      (node (ref "R11") (pin "1") (pinfunction "1_1") (pintype "passive"))
      (node (ref "R12") (pin "1") (pinfunction "1_1") (pintype "passive"))
      (node (ref "R13") (pin "1") (pinfunction "1_1") (pintype "passive"))
      (node (ref "R14") (pin "1") (pinfunction "1_1") (pintype "passive"))
      (node (ref "R15") (pin "1") (pinfunction "1_1") (pintype "passive"))
      (node (ref "R16") (pin "1") (pinfunction "1_1") (pintype "passive"))
      (node (ref "R17") (pin "1") (pinfunction "1_1") (pintype "passive"))
      (node (ref "SL1") (pin "2") (pinfunction "S_2") (pintype "passive"))
      (node (ref "SL1") (pin "3") (pinfunction "S_3") (pintype "passive"))
    )
    (net (code "40") (name "INIT") (class "Default")
      (node (ref "E1") (pin "8") (pinfunction "O_8") (pintype "output"))
      (node (ref "E15") (pin "4") (pinfunction "I0_4") (pintype "input"))
      (node (ref "E15") (pin "5") (pinfunction "I1_5") (pintype "input"))
      (node (ref "E18") (pin "12") (pinfunction "I1_12") (pintype "input"))
      (node (ref "E26") (pin "2") (pinfunction "I0_2") (pintype "input"))
      (node (ref "E26") (pin "5") (pinfunction "I0_5") (pintype "input"))
      (node (ref "E26") (pin "8") (pinfunction "I0_8") (pintype "input"))
      (node (ref "IC8") (pin "6") (pinfunction "I0_6") (pintype "input"))
      (node (ref "IC8") (pin "7") (pinfunction "I1_7") (pintype "input"))
    )
    (net (code "41") (name "MAINT") (class "Default")
      (node (ref "E32") (pin "9") (pinfunction "I0_9") (pintype "input"))
      (node (ref "E35") (pin "3") (pinfunction "I1_3") (pintype "input"))
      (node (ref "E35") (pin "6") (pinfunction "I1_6") (pintype "input"))
      (node (ref "E35") (pin "9") (pinfunction "I1_9") (pintype "input"))
      (node (ref "E36") (pin "2") (pinfunction "I0_2") (pintype "input"))
      (node (ref "E36") (pin "6") (pinfunction "I1_6") (pintype "input"))
      (node (ref "E36") (pin "9") (pinfunction "I1_9") (pintype "input"))
      (node (ref "E6") (pin "5") (pinfunction "Q_5") (pintype "output"))
    )
    (net (code "42") (name "MSB8") (class "Default")
      (node (ref "E21") (pin "12") (pinfunction "QD_12") (pintype "output"))
      (node (ref "E23") (pin "2") (pinfunction "J_2") (pintype "input"))
      (node (ref "E23") (pin "3") (pinfunction "K_3") (pintype "input"))
      (node (ref "E8") (pin "5") (pinfunction "I2_5") (pintype "input"))
      (node (ref "IC1") (pin "6") (pinfunction "I0_6") (pintype "input"))
    )
    (net (code "43") (name "MSB12") (class "Default")
      (node (ref "E23") (pin "12") (pinfunction "QD_12") (pintype "output"))
      (node (ref "E8") (pin "2") (pinfunction "I1_2") (pintype "input"))
      (node (ref "IC6") (pin "1") (pinfunction "I0_1") (pintype "input"))
    )
    (net (code "44") (name "Net-(70-P)") (class "Default")
      (node (ref "70") (pin "1") (pinfunction "P_1") (pintype "passive"))
      (node (ref "E14") (pin "15") (pinfunction "Y0_15") (pintype "output"))
    )
    (net (code "45") (name "Net-(71-P)") (class "Default")
      (node (ref "71") (pin "1") (pinfunction "P_1") (pintype "passive"))
      (node (ref "E14") (pin "14") (pinfunction "Y1_14") (pintype "output"))
    )
    (net (code "46") (name "Net-(72-P)") (class "Default")
      (node (ref "72") (pin "1") (pinfunction "P_1") (pintype "passive"))
      (node (ref "E14") (pin "13") (pinfunction "Y2_13") (pintype "output"))
    )
    (net (code "47") (name "Net-(73-P)") (class "Default")
      (node (ref "73") (pin "1") (pinfunction "P_1") (pintype "passive"))
      (node (ref "E14") (pin "12") (pinfunction "Y3_12") (pintype "output"))
    )
    (net (code "48") (name "Net-(74-P)") (class "Default")
      (node (ref "74") (pin "1") (pinfunction "P_1") (pintype "passive"))
      (node (ref "E14") (pin "11") (pinfunction "Y4_11") (pintype "output"))
    )
    (net (code "49") (name "Net-(75-P)") (class "Default")
      (node (ref "75") (pin "1") (pinfunction "P_1") (pintype "passive"))
      (node (ref "E14") (pin "10") (pinfunction "Y5_10") (pintype "output"))
    )
    (net (code "50") (name "Net-(76-P)") (class "Default")
      (node (ref "76") (pin "1") (pinfunction "P_1") (pintype "passive"))
      (node (ref "E14") (pin "9") (pinfunction "Y6_9") (pintype "output"))
    )
    (net (code "51") (name "Net-(77-P)") (class "Default")
      (node (ref "77") (pin "1") (pinfunction "P_1") (pintype "passive"))
      (node (ref "E14") (pin "7") (pinfunction "Y7_7") (pintype "output"))
    )
    (net (code "52") (name "Net-(E1B-O)") (class "Default")
      (node (ref "E1") (pin "10") (pinfunction "I1_10") (pintype "input"))
      (node (ref "E1") (pin "6") (pinfunction "O_6") (pintype "output"))
      (node (ref "E1") (pin "9") (pinfunction "I0_9") (pintype "input"))
      (node (ref "E2") (pin "1") (pinfunction "CLR_1") (pintype "input"))
    )
    (net (code "53") (name "Net-(E1C-I2)") (class "Default")
      (node (ref "E1") (pin "11") (pinfunction "I2_11") (pintype "input"))
      (node (ref "E2") (pin "6") (pinfunction "~{Q}_6") (pintype "output"))
    )
    (net (code "54") (name "Net-(E4A-A)") (class "Default")
      (node (ref "E4") (pin "10") (pinfunction "ENT_10") (pintype "input"))
      (node (ref "E4") (pin "3") (pinfunction "A_3") (pintype "input"))
      (node (ref "E4") (pin "4") (pinfunction "B_4") (pintype "input"))
      (node (ref "E4") (pin "7") (pinfunction "ENP_7") (pintype "input"))
      (node (ref "R19") (pin "2") (pinfunction "2_2") (pintype "passive"))
    )
    (net (code "55") (name "Net-(E4A-C)") (class "Default")
      (node (ref "E4") (pin "5") (pinfunction "C_5") (pintype "input"))
      (node (ref "E5") (pin "3") (pinfunction "O_3") (pintype "output"))
    )
    (net (code "56") (name "Net-(E5A-I0)") (class "Default")
      (node (ref "E5") (pin "1") (pinfunction "I0_1") (pintype "input"))
      (node (ref "E5") (pin "11") (pinfunction "O_11") (pintype "output"))
    )
    (net (code "57") (name "Net-(E8A-O)") (class "Default")
      (node (ref "E8") (pin "11") (pinfunction "I2_11") (pintype "input"))
      (node (ref "E8") (pin "12") (pinfunction "O_12") (pintype "output"))
    )
    (net (code "58") (name "Net-(E8B-O)") (class "Default")
      (node (ref "E8") (pin "6") (pinfunction "O_6") (pintype "output"))
      (node (ref "E8") (pin "9") (pinfunction "I0_9") (pintype "input"))
    )
    (net (code "59") (name "Net-(E10A-I0)") (class "Default")
      (node (ref "E10") (pin "1") (pinfunction "I0_1") (pintype "input"))
      (node (ref "E10") (pin "6") (pinfunction "O_6") (pintype "output"))
    )
    (net (code "60") (name "Net-(E10A-O)") (class "Default")
      (node (ref "E10") (pin "10") (pinfunction "I1_10") (pintype "input"))
      (node (ref "E10") (pin "11") (pinfunction "I2_11") (pintype "input"))
      (node (ref "E10") (pin "12") (pinfunction "O_12") (pintype "output"))
    )
    (net (code "61") (name "Net-(E10C-O)") (class "Default")
      (node (ref "E10") (pin "8") (pinfunction "O_8") (pintype "output"))
      (node (ref "IC7") (pin "1") (pinfunction "I0_1") (pintype "input"))
      (node (ref "IC7") (pin "2") (pinfunction "I1_2") (pintype "input"))
    )
    (net (code "62") (name "Net-(E14A-G2A)") (class "Default")
      (node (ref "E1") (pin "12") (pinfunction "O_12") (pintype "output"))
      (node (ref "E14") (pin "4") (pinfunction "G2A_4") (pintype "input"))
      (node (ref "E14") (pin "5") (pinfunction "G2B_5") (pintype "input"))
    )
    (net (code "63") (name "Net-(E15A-O)") (class "Default")
      (node (ref "E15") (pin "3") (pinfunction "O_3") (pintype "output"))
      (node (ref "E8") (pin "13") (pinfunction "I2_13") (pintype "input"))
      (node (ref "E8") (pin "3") (pinfunction "I0_3") (pintype "input"))
    )
    (net (code "64") (name "Net-(E15C-I0)") (class "Default")
      (node (ref "E15") (pin "9") (pinfunction "I0_9") (pintype "input"))
      (node (ref "E20") (pin "11") (pinfunction "O_11") (pintype "output"))
      (node (ref "E24") (pin "10") (pinfunction "I1_10") (pintype "input"))
    )
    (net (code "65") (name "Net-(E15C-O)") (class "Default")
      (node (ref "E15") (pin "8") (pinfunction "O_8") (pintype "output"))
      (node (ref "E24") (pin "12") (pinfunction "I0_12") (pintype "input"))
    )
    (net (code "66") (name "Net-(E15D-O)") (class "Default")
      (node (ref "E15") (pin "11") (pinfunction "O_11") (pintype "output"))
      (node (ref "E8") (pin "10") (pinfunction "I1_10") (pintype "input"))
    )
    (net (code "67") (name "Net-(E16A-A)") (class "Default")
      (node (ref "E16") (pin "4") (pinfunction "A_4") (pintype "input"))
      (node (ref "E19") (pin "6") (pinfunction "~{Q}_6") (pintype "output"))
    )
    (net (code "68") (name "Net-(E16A-B)") (class "Default")
      (node (ref "E16") (pin "5") (pinfunction "B_5") (pintype "input"))
      (node (ref "E19") (pin "8") (pinfunction "~{Q}_8") (pintype "output"))
    )
    (net (code "69") (name "Net-(E16A-C)") (class "Default")
      (node (ref "E16") (pin "6") (pinfunction "C_6") (pintype "input"))
      (node (ref "E16") (pin "7") (pinfunction "D_7") (pintype "input"))
      (node (ref "E6") (pin "8") (pinfunction "~{Q}_8") (pintype "output"))
    )
    (net (code "70") (name "Net-(E17B-CLR)") (class "Default")
      (node (ref "E17") (pin "8") (pinfunction "CLR_8") (pintype "input"))
      (node (ref "E18") (pin "13") (pinfunction "O_13") (pintype "output"))
    )
    (net (code "71") (name "Net-(E17B-J)") (class "Default")
      (node (ref "E17") (pin "12") (pinfunction "K_12") (pintype "input"))
      (node (ref "E17") (pin "9") (pinfunction "J_9") (pintype "input"))
      (node (ref "E8") (pin "8") (pinfunction "O_8") (pintype "output"))
      (node (ref "IC7") (pin "7") (pinfunction "I1_7") (pintype "input"))
    )
    (net (code "72") (name "Net-(E19A-CLR)") (class "Default")
      (node (ref "E19") (pin "1") (pinfunction "CLR_1") (pintype "input"))
      (node (ref "E26") (pin "1") (pinfunction "O_1") (pintype "output"))
    )
    (net (code "73") (name "Net-(E19B-CLR)") (class "Default")
      (node (ref "E19") (pin "13") (pinfunction "CLR_13") (pintype "input"))
      (node (ref "E26") (pin "4") (pinfunction "O_4") (pintype "output"))
    )
    (net (code "74") (name "Net-(E20A-I1)") (class "Default")
      (node (ref "E20") (pin "2") (pinfunction "I1_2") (pintype "input"))
      (node (ref "E20") (pin "6") (pinfunction "O_6") (pintype "output"))
    )
    (net (code "75") (name "Net-(E20A-O)") (class "Default")
      (node (ref "E20") (pin "3") (pinfunction "O_3") (pintype "output"))
      (node (ref "IC10") (pin "1") (pinfunction "I0_1") (pintype "input"))
      (node (ref "IC10") (pin "2") (pinfunction "I1_2") (pintype "input"))
    )
    (net (code "76") (name "Net-(E21A-J)") (class "Default")
      (node (ref "E21") (pin "2") (pinfunction "J_2") (pintype "input"))
      (node (ref "E21") (pin "3") (pinfunction "K_3") (pintype "input"))
      (node (ref "E22") (pin "12") (pinfunction "QD_12") (pintype "output"))
      (node (ref "IC4") (pin "6") (pinfunction "I0_6") (pintype "input"))
    )
    (net (code "77") (name "Net-(E21A-QA)") (class "Default")
      (node (ref "E21") (pin "15") (pinfunction "QA_15") (pintype "output"))
      (node (ref "IC3") (pin "6") (pinfunction "I0_6") (pintype "input"))
    )
    (net (code "78") (name "Net-(E21A-QB)") (class "Default")
      (node (ref "E21") (pin "14") (pinfunction "QB_14") (pintype "output"))
      (node (ref "IC3") (pin "1") (pinfunction "I0_1") (pintype "input"))
    )
    (net (code "79") (name "Net-(E21A-QC)") (class "Default")
      (node (ref "E21") (pin "13") (pinfunction "QC_13") (pintype "output"))
      (node (ref "IC4") (pin "1") (pinfunction "I0_1") (pintype "input"))
    )
    (net (code "80") (name "Net-(E22A-QA)") (class "Default")
      (node (ref "E22") (pin "15") (pinfunction "QA_15") (pintype "output"))
      (node (ref "IC2") (pin "1") (pinfunction "I0_1") (pintype "input"))
    )
    (net (code "81") (name "Net-(E22A-QB)") (class "Default")
      (node (ref "E22") (pin "14") (pinfunction "QB_14") (pintype "output"))
      (node (ref "IC5") (pin "6") (pinfunction "I0_6") (pintype "input"))
    )
    (net (code "82") (name "Net-(E22A-QC)") (class "Default")
      (node (ref "E22") (pin "13") (pinfunction "QC_13") (pintype "output"))
      (node (ref "IC5") (pin "1") (pinfunction "I0_1") (pintype "input"))
    )
    (net (code "83") (name "Net-(E23A-QA)") (class "Default")
      (node (ref "E23") (pin "15") (pinfunction "QA_15") (pintype "output"))
      (node (ref "IC2") (pin "6") (pinfunction "I0_6") (pintype "input"))
    )
    (net (code "84") (name "Net-(E23A-QB)") (class "Default")
      (node (ref "E23") (pin "14") (pinfunction "QB_14") (pintype "output"))
      (node (ref "IC1") (pin "1") (pinfunction "I0_1") (pintype "input"))
    )
    (net (code "85") (name "Net-(E23A-QC)") (class "Default")
      (node (ref "E23") (pin "13") (pinfunction "QC_13") (pintype "output"))
      (node (ref "IC6") (pin "6") (pinfunction "I0_6") (pintype "input"))
    )
    (net (code "86") (name "Net-(E24A-I1)") (class "Default")
      (node (ref "E24") (pin "2") (pinfunction "I1_2") (pintype "input"))
      (node (ref "E35") (pin "13") (pinfunction "O_13") (pintype "output"))
      (node (ref "IC1") (pin "7") (pinfunction "I1_7") (pintype "input"))
      (node (ref "IC2") (pin "2") (pinfunction "I1_2") (pintype "input"))
      (node (ref "IC3") (pin "2") (pinfunction "I1_2") (pintype "input"))
      (node (ref "IC3") (pin "7") (pinfunction "I1_7") (pintype "input"))
      (node (ref "IC4") (pin "2") (pinfunction "I1_2") (pintype "input"))
      (node (ref "IC4") (pin "7") (pinfunction "I1_7") (pintype "input"))
      (node (ref "IC5") (pin "2") (pinfunction "I1_2") (pintype "input"))
      (node (ref "IC5") (pin "7") (pinfunction "I1_7") (pintype "input"))
    )
    (net (code "87") (name "Net-(E24A-O)") (class "Default")
      (node (ref "E24") (pin "3") (pinfunction "O_3") (pintype "output"))
      (node (ref "IC1") (pin "2") (pinfunction "I1_2") (pintype "input"))
      (node (ref "IC2") (pin "7") (pinfunction "I1_7") (pintype "input"))
      (node (ref "IC6") (pin "2") (pinfunction "I1_2") (pintype "input"))
      (node (ref "IC6") (pin "7") (pinfunction "I1_7") (pintype "input"))
    )
    (net (code "88") (name "Net-(E24B-O)") (class "Default")
      (node (ref "E24") (pin "6") (pinfunction "O_6") (pintype "output"))
      (node (ref "E32") (pin "1") (pinfunction "I0_1") (pintype "input"))
    )
    (net (code "89") (name "Net-(E24C-O)") (class "Default")
      (node (ref "E24") (pin "8") (pinfunction "O_8") (pintype "output"))
      (node (ref "E30") (pin "13") (pinfunction "CLR_13") (pintype "input"))
    )
    (net (code "90") (name "Net-(E25C-O)") (class "Default")
      (node (ref "E25") (pin "6") (pinfunction "O_6") (pintype "output"))
      (node (ref "E31") (pin "1") (pinfunction "I0_1") (pintype "input"))
      (node (ref "E31") (pin "2") (pinfunction "I1_2") (pintype "input"))
    )
    (net (code "91") (name "Net-(E25D-O)") (class "Default")
      (node (ref "E25") (pin "8") (pinfunction "O_8") (pintype "output"))
      (node (ref "E31") (pin "13") (pinfunction "I3_13") (pintype "input"))
    )
    (net (code "92") (name "Net-(E25E-O)") (class "Default")
      (node (ref "E25") (pin "10") (pinfunction "O_10") (pintype "output"))
      (node (ref "E26") (pin "11") (pinfunction "I0_11") (pintype "input"))
      (node (ref "E26") (pin "12") (pinfunction "I1_12") (pintype "input"))
    )
    (net (code "93") (name "Net-(E25F-O)") (class "Default")
      (node (ref "E25") (pin "12") (pinfunction "O_12") (pintype "output"))
      (node (ref "E36") (pin "11") (pinfunction "I0_11") (pintype "input"))
      (node (ref "E36") (pin "12") (pinfunction "I1_12") (pintype "input"))
    )
    (net (code "94") (name "Net-(E26C-O)") (class "Default")
      (node (ref "E26") (pin "10") (pinfunction "O_10") (pintype "output"))
      (node (ref "E6") (pin "13") (pinfunction "CLR_13") (pintype "input"))
    )
    (net (code "95") (name "Net-(E30A-Q)") (class "Default")
      (node (ref "E30") (pin "5") (pinfunction "Q_5") (pintype "output"))
      (node (ref "IC10") (pin "7") (pinfunction "I1_7") (pintype "input"))
    )
    (net (code "96") (name "Net-(E30B-CLK)") (class "Default")
      (node (ref "E30") (pin "11") (pinfunction "CLK_11") (pintype "input"))
      (node (ref "IC9") (pin "3") (pinfunction "O_3") (pintype "open_collector"))
      (node (ref "R18") (pin "1") (pinfunction "1_1") (pintype "passive"))
    )
    (net (code "97") (name "Net-(E31A-O)") (class "Default")
      (node (ref "E31") (pin "6") (pinfunction "O_6") (pintype "output"))
      (node (ref "IC9") (pin "1") (pinfunction "I0_1") (pintype "input"))
    )
    (net (code "98") (name "Net-(E31B-O)") (class "Default")
      (node (ref "E31") (pin "8") (pinfunction "O_8") (pintype "output"))
      (node (ref "IC9") (pin "2") (pinfunction "I1_2") (pintype "input"))
    )
    (net (code "99") (name "Net-(E32A-O)") (class "Default")
      (node (ref "E32") (pin "12") (pinfunction "O_12") (pintype "output"))
      (node (ref "E32") (pin "4") (pinfunction "I1_4") (pintype "input"))
      (node (ref "E32") (pin "5") (pinfunction "I2_5") (pintype "input"))
    )
    (net (code "100") (name "Net-(E32C-O)") (class "Default")
      (node (ref "E32") (pin "8") (pinfunction "O_8") (pintype "output"))
      (node (ref "E35") (pin "11") (pinfunction "I0_11") (pintype "input"))
    )
    (net (code "101") (name "Net-(PAD10-P)") (class "Default")
      (node (ref "E38") (pin "1") (pinfunction "1_1") (pintype "passive"))
      (node (ref "PAD10") (pin "1") (pinfunction "P_1") (pintype "passive"))
    )
    (net (code "102") (name "Net-(PAD11-P)") (class "Default")
      (node (ref "E38") (pin "2") (pinfunction "2_2") (pintype "passive"))
      (node (ref "PAD11") (pin "1") (pinfunction "P_1") (pintype "passive"))
    )
    (net (code "103") (name "Net-(PAD12-P)") (class "Default")
      (node (ref "E38") (pin "3") (pinfunction "3_3") (pintype "passive"))
      (node (ref "PAD12") (pin "1") (pinfunction "P_1") (pintype "passive"))
    )
    (net (code "104") (name "Net-(PAD13-P)") (class "Default")
      (node (ref "E38") (pin "4") (pinfunction "4_4") (pintype "passive"))
      (node (ref "PAD13") (pin "1") (pinfunction "P_1") (pintype "passive"))
    )
    (net (code "105") (name "Net-(PAD14-P)") (class "Default")
      (node (ref "E38") (pin "5") (pinfunction "5_5") (pintype "passive"))
      (node (ref "PAD14") (pin "1") (pinfunction "P_1") (pintype "passive"))
    )
    (net (code "106") (name "Net-(PAD15-P)") (class "Default")
      (node (ref "E38") (pin "6") (pinfunction "6_6") (pintype "passive"))
      (node (ref "PAD15") (pin "1") (pinfunction "P_1") (pintype "passive"))
    )
    (net (code "107") (name "Net-(PAD16-P)") (class "Default")
      (node (ref "E38") (pin "7") (pinfunction "7_7") (pintype "passive"))
      (node (ref "PAD16") (pin "1") (pinfunction "P_1") (pintype "passive"))
    )
    (net (code "108") (name "Net-(PAD17-P)") (class "Default")
      (node (ref "E38") (pin "8") (pinfunction "8_8") (pintype "passive"))
      (node (ref "PAD17") (pin "1") (pinfunction "P_1") (pintype "passive"))
    )
    (net (code "109") (name "Net-(PAD18-P)") (class "Default")
      (node (ref "E40") (pin "1") (pinfunction "1_1") (pintype "passive"))
      (node (ref "PAD18") (pin "1") (pinfunction "P_1") (pintype "passive"))
    )
    (net (code "110") (name "Net-(PAD19-P)") (class "Default")
      (node (ref "E40") (pin "2") (pinfunction "2_2") (pintype "passive"))
      (node (ref "PAD19") (pin "1") (pinfunction "P_1") (pintype "passive"))
    )
    (net (code "111") (name "Net-(PAD20-P)") (class "Default")
      (node (ref "E38") (pin "16") (pinfunction "16_16") (pintype "passive"))
      (node (ref "PAD20") (pin "1") (pinfunction "P_1") (pintype "passive"))
    )
    (net (code "112") (name "Net-(PAD21-P)") (class "Default")
      (node (ref "E38") (pin "15") (pinfunction "15_15") (pintype "passive"))
      (node (ref "PAD21") (pin "1") (pinfunction "P_1") (pintype "passive"))
    )
    (net (code "113") (name "Net-(PAD22-P)") (class "Default")
      (node (ref "E38") (pin "14") (pinfunction "14_14") (pintype "passive"))
      (node (ref "PAD22") (pin "1") (pinfunction "P_1") (pintype "passive"))
    )
    (net (code "114") (name "Net-(PAD23-P)") (class "Default")
      (node (ref "E38") (pin "13") (pinfunction "13_13") (pintype "passive"))
      (node (ref "PAD23") (pin "1") (pinfunction "P_1") (pintype "passive"))
    )
    (net (code "115") (name "Net-(PAD24-P)") (class "Default")
      (node (ref "E38") (pin "12") (pinfunction "12_12") (pintype "passive"))
      (node (ref "PAD24") (pin "1") (pinfunction "P_1") (pintype "passive"))
    )
    (net (code "116") (name "Net-(PAD25-P)") (class "Default")
      (node (ref "E38") (pin "11") (pinfunction "11_11") (pintype "passive"))
      (node (ref "PAD25") (pin "1") (pinfunction "P_1") (pintype "passive"))
    )
    (net (code "117") (name "Net-(PAD26-P)") (class "Default")
      (node (ref "E38") (pin "10") (pinfunction "10_10") (pintype "passive"))
      (node (ref "PAD26") (pin "1") (pinfunction "P_1") (pintype "passive"))
    )
    (net (code "118") (name "Net-(PAD27-P)") (class "Default")
      (node (ref "E38") (pin "9") (pinfunction "9_9") (pintype "passive"))
      (node (ref "PAD27") (pin "1") (pinfunction "P_1") (pintype "passive"))
    )
    (net (code "119") (name "Net-(PAD28-P)") (class "Default")
      (node (ref "E40") (pin "3") (pinfunction "3_3") (pintype "passive"))
      (node (ref "PAD28") (pin "1") (pinfunction "P_1") (pintype "passive"))
    )
    (net (code "120") (name "Net-(PAD29-P)") (class "Default")
      (node (ref "E40") (pin "4") (pinfunction "4_4") (pintype "passive"))
      (node (ref "PAD29") (pin "1") (pinfunction "P_1") (pintype "passive"))
    )
    (net (code "121") (name "Net-(PAD30-P)") (class "Default")
      (node (ref "E40") (pin "5") (pinfunction "5_5") (pintype "passive"))
      (node (ref "PAD30") (pin "1") (pinfunction "P_1") (pintype "passive"))
    )
    (net (code "122") (name "Net-(PAD31-P)") (class "Default")
      (node (ref "E40") (pin "6") (pinfunction "6_6") (pintype "passive"))
      (node (ref "PAD31") (pin "1") (pinfunction "P_1") (pintype "passive"))
    )
    (net (code "123") (name "Net-(PAD32-P)") (class "Default")
      (node (ref "E40") (pin "7") (pinfunction "7_7") (pintype "passive"))
      (node (ref "PAD32") (pin "1") (pinfunction "P_1") (pintype "passive"))
    )
    (net (code "124") (name "Net-(PAD33-P)") (class "Default")
      (node (ref "E40") (pin "8") (pinfunction "8_8") (pintype "passive"))
      (node (ref "PAD33") (pin "1") (pinfunction "P_1") (pintype "passive"))
    )
    (net (code "125") (name "Net-(PAD34-P)") (class "Default")
      (node (ref "E40") (pin "16") (pinfunction "16_16") (pintype "passive"))
      (node (ref "PAD34") (pin "1") (pinfunction "P_1") (pintype "passive"))
    )
    (net (code "126") (name "Net-(PAD35-P)") (class "Default")
      (node (ref "E40") (pin "15") (pinfunction "15_15") (pintype "passive"))
      (node (ref "PAD35") (pin "1") (pinfunction "P_1") (pintype "passive"))
    )
    (net (code "127") (name "Net-(PAD36-P)") (class "Default")
      (node (ref "E40") (pin "14") (pinfunction "14_14") (pintype "passive"))
      (node (ref "PAD36") (pin "1") (pinfunction "P_1") (pintype "passive"))
    )
    (net (code "128") (name "Net-(PAD37-P)") (class "Default")
      (node (ref "E40") (pin "13") (pinfunction "13_13") (pintype "passive"))
      (node (ref "PAD37") (pin "1") (pinfunction "P_1") (pintype "passive"))
    )
    (net (code "129") (name "Net-(PAD38-P)") (class "Default")
      (node (ref "E40") (pin "12") (pinfunction "12_12") (pintype "passive"))
      (node (ref "PAD38") (pin "1") (pinfunction "P_1") (pintype "passive"))
    )
    (net (code "130") (name "Net-(PAD39-P)") (class "Default")
      (node (ref "E40") (pin "11") (pinfunction "11_11") (pintype "passive"))
      (node (ref "PAD39") (pin "1") (pinfunction "P_1") (pintype "passive"))
    )
    (net (code "131") (name "Net-(PAD40-P)") (class "Default")
      (node (ref "E40") (pin "10") (pinfunction "10_10") (pintype "passive"))
      (node (ref "PAD40") (pin "1") (pinfunction "P_1") (pintype "passive"))
    )
    (net (code "132") (name "Net-(PAD41-P)") (class "Default")
      (node (ref "E40") (pin "9") (pinfunction "9_9") (pintype "passive"))
      (node (ref "PAD41") (pin "1") (pinfunction "P_1") (pintype "passive"))
    )
    (net (code "133") (name "Net-(PAD42-P)") (class "Default")
      (node (ref "E39") (pin "1") (pinfunction "1_1") (pintype "passive"))
      (node (ref "PAD42") (pin "1") (pinfunction "P_1") (pintype "passive"))
    )
    (net (code "134") (name "Net-(PAD43-P)") (class "Default")
      (node (ref "E39") (pin "2") (pinfunction "2_2") (pintype "passive"))
      (node (ref "PAD43") (pin "1") (pinfunction "P_1") (pintype "passive"))
    )
    (net (code "135") (name "Net-(PAD44-P)") (class "Default")
      (node (ref "E39") (pin "3") (pinfunction "3_3") (pintype "passive"))
      (node (ref "PAD44") (pin "1") (pinfunction "P_1") (pintype "passive"))
    )
    (net (code "136") (name "Net-(PAD45-P)") (class "Default")
      (node (ref "E39") (pin "4") (pinfunction "4_4") (pintype "passive"))
      (node (ref "PAD45") (pin "1") (pinfunction "P_1") (pintype "passive"))
    )
    (net (code "137") (name "Net-(PAD46-P)") (class "Default")
      (node (ref "E39") (pin "5") (pinfunction "5_5") (pintype "passive"))
      (node (ref "PAD46") (pin "1") (pinfunction "P_1") (pintype "passive"))
    )
    (net (code "138") (name "Net-(PAD47-P)") (class "Default")
      (node (ref "E39") (pin "6") (pinfunction "6_6") (pintype "passive"))
      (node (ref "PAD47") (pin "1") (pinfunction "P_1") (pintype "passive"))
    )
    (net (code "139") (name "Net-(PAD48-P)") (class "Default")
      (node (ref "E39") (pin "7") (pinfunction "7_7") (pintype "passive"))
      (node (ref "PAD48") (pin "1") (pinfunction "P_1") (pintype "passive"))
    )
    (net (code "140") (name "Net-(PAD49-P)") (class "Default")
      (node (ref "E39") (pin "8") (pinfunction "8_8") (pintype "passive"))
      (node (ref "PAD49") (pin "1") (pinfunction "P_1") (pintype "passive"))
    )
    (net (code "141") (name "Net-(PAD50-P)") (class "Default")
      (node (ref "E39") (pin "16") (pinfunction "16_16") (pintype "passive"))
      (node (ref "PAD50") (pin "1") (pinfunction "P_1") (pintype "passive"))
    )
    (net (code "142") (name "Net-(PAD51-P)") (class "Default")
      (node (ref "E39") (pin "15") (pinfunction "15_15") (pintype "passive"))
      (node (ref "PAD51") (pin "1") (pinfunction "P_1") (pintype "passive"))
    )
    (net (code "143") (name "Net-(PAD52-P)") (class "Default")
      (node (ref "E39") (pin "14") (pinfunction "14_14") (pintype "passive"))
      (node (ref "PAD52") (pin "1") (pinfunction "P_1") (pintype "passive"))
    )
    (net (code "144") (name "Net-(PAD53-P)") (class "Default")
      (node (ref "E39") (pin "13") (pinfunction "13_13") (pintype "passive"))
      (node (ref "PAD53") (pin "1") (pinfunction "P_1") (pintype "passive"))
    )
    (net (code "145") (name "Net-(PAD54-P)") (class "Default")
      (node (ref "E39") (pin "12") (pinfunction "12_12") (pintype "passive"))
      (node (ref "PAD54") (pin "1") (pinfunction "P_1") (pintype "passive"))
    )
    (net (code "146") (name "Net-(PAD55-P)") (class "Default")
      (node (ref "E39") (pin "11") (pinfunction "11_11") (pintype "passive"))
      (node (ref "PAD55") (pin "1") (pinfunction "P_1") (pintype "passive"))
    )
    (net (code "147") (name "Net-(PAD56-P)") (class "Default")
      (node (ref "E39") (pin "10") (pinfunction "10_10") (pintype "passive"))
      (node (ref "PAD56") (pin "1") (pinfunction "P_1") (pintype "passive"))
    )
    (net (code "148") (name "Net-(PAD57-P)") (class "Default")
      (node (ref "E39") (pin "9") (pinfunction "9_9") (pintype "passive"))
      (node (ref "PAD57") (pin "1") (pinfunction "P_1") (pintype "passive"))
    )
    (net (code "149") (name "RD") (class "Default")
      (node (ref "E25") (pin "1") (pinfunction "I_1") (pintype "input"))
      (node (ref "E32") (pin "10") (pinfunction "I1_10") (pintype "input"))
      (node (ref "E35") (pin "10") (pinfunction "O_10") (pintype "output"))
    )
    (net (code "150") (name "RUN") (class "Default")
      (node (ref "E18") (pin "11") (pinfunction "I0_11") (pintype "input"))
      (node (ref "E30") (pin "9") (pinfunction "Q_9") (pintype "output"))
      (node (ref "IC9") (pin "6") (pinfunction "I0_6") (pintype "input"))
      (node (ref "IC9") (pin "7") (pinfunction "I1_7") (pintype "input"))
    )
    (net (code "151") (name "RX_DATA") (class "Default")
      (node (ref "E22") (pin "2") (pinfunction "J_2") (pintype "input"))
      (node (ref "E22") (pin "3") (pinfunction "K_3") (pintype "input"))
      (node (ref "E35") (pin "1") (pinfunction "O_1") (pintype "output"))
    )
    (net (code "152") (name "RX_DONE") (class "Default")
      (node (ref "E20") (pin "13") (pinfunction "I1_13") (pintype "input"))
      (node (ref "E25") (pin "3") (pinfunction "I_3") (pintype "input"))
      (node (ref "E31") (pin "4") (pinfunction "I2_4") (pintype "input"))
      (node (ref "E32") (pin "11") (pinfunction "I2_11") (pintype "input"))
      (node (ref "E36") (pin "10") (pinfunction "O_10") (pintype "output"))
      (node (ref "E6") (pin "11") (pinfunction "CLK_11") (pintype "input"))
    )
    (net (code "153") (name "SHIFT") (class "Default")
      (node (ref "E32") (pin "3") (pinfunction "I0_3") (pintype "input"))
      (node (ref "E35") (pin "4") (pinfunction "O_4") (pintype "output"))
    )
    (net (code "154") (name "TR_SKIP") (class "Default")
      (node (ref "E18") (pin "1") (pinfunction "O_1") (pintype "output"))
      (node (ref "E20") (pin "1") (pinfunction "I0_1") (pintype "input"))
      (node (ref "E26") (pin "3") (pinfunction "I1_3") (pintype "input"))
    )
    (net (code "155") (name "VCC") (class "Default")
      (node (ref "C1") (pin "1") (pinfunction "1_1") (pintype "passive"))
      (node (ref "C10") (pin "1") (pinfunction "1_1") (pintype "passive"))
      (node (ref "C11") (pin "1") (pinfunction "1_1") (pintype "passive"))
      (node (ref "C12") (pin "1") (pinfunction "1_1") (pintype "passive"))
      (node (ref "C13") (pin "1") (pinfunction "1_1") (pintype "passive"))
      (node (ref "C14") (pin "1") (pinfunction "1_1") (pintype "passive"))
      (node (ref "C15") (pin "1") (pinfunction "1_1") (pintype "passive"))
      (node (ref "C16") (pin "1") (pinfunction "1_1") (pintype "passive"))
      (node (ref "C17") (pin "1") (pinfunction "1_1") (pintype "passive"))
      (node (ref "C18") (pin "1") (pinfunction "1_1") (pintype "passive"))
      (node (ref "C19") (pin "1") (pinfunction "1_1") (pintype "passive"))
      (node (ref "C2") (pin "1") (pinfunction "1_1") (pintype "passive"))
      (node (ref "C20") (pin "1") (pinfunction "1_1") (pintype "passive"))
      (node (ref "C21") (pin "1") (pinfunction "1_1") (pintype "passive"))
      (node (ref "C22") (pin "1") (pinfunction "1_1") (pintype "passive"))
      (node (ref "C23") (pin "1") (pinfunction "1_1") (pintype "passive"))
      (node (ref "C24") (pin "1") (pinfunction "1_1") (pintype "passive"))
      (node (ref "C25") (pin "1") (pinfunction "1_1") (pintype "passive"))
      (node (ref "C26") (pin "1") (pinfunction "1_1") (pintype "passive"))
      (node (ref "C27") (pin "1") (pinfunction "1_1") (pintype "passive"))
      (node (ref "C28") (pin "1") (pinfunction "1_1") (pintype "passive"))
      (node (ref "C29") (pin "1") (pinfunction "1_1") (pintype "passive"))
      (node (ref "C3") (pin "1") (pinfunction "1_1") (pintype "passive"))
      (node (ref "C30") (pin "1") (pinfunction "1_1") (pintype "passive"))
      (node (ref "C31") (pin "1") (pinfunction "1_1") (pintype "passive"))
      (node (ref "C32") (pin "1") (pinfunction "1_1") (pintype "passive"))
      (node (ref "C33") (pin "1") (pinfunction "1_1") (pintype "passive"))
      (node (ref "C34") (pin "1") (pinfunction "1_1") (pintype "passive"))
      (node (ref "C35") (pin "1") (pinfunction "1_1") (pintype "passive"))
      (node (ref "C36") (pin "1") (pinfunction "1_1") (pintype "passive"))
      (node (ref "C37") (pin "1") (pinfunction "1_1") (pintype "passive"))
      (node (ref "C38") (pin "1") (pinfunction "1_1") (pintype "passive"))
      (node (ref "C39") (pin "1") (pinfunction "1_1") (pintype "passive"))
      (node (ref "C4") (pin "1") (pinfunction "1_1") (pintype "passive"))
      (node (ref "C40") (pin "+") (pinfunction "+_+") (pintype "passive"))
      (node (ref "C5") (pin "1") (pinfunction "1_1") (pintype "passive"))
      (node (ref "C6") (pin "1") (pinfunction "1_1") (pintype "passive"))
      (node (ref "C7") (pin "1") (pinfunction "1_1") (pintype "passive"))
      (node (ref "C8") (pin "1") (pinfunction "1_1") (pintype "passive"))
      (node (ref "C9") (pin "1") (pinfunction "1_1") (pintype "passive"))
      (node (ref "E1") (pin "4") (pinfunction "I1_4") (pintype "input"))
      (node (ref "E1") (pin "5") (pinfunction "I2_5") (pintype "input"))
      (node (ref "E14") (pin "6") (pinfunction "G1_6") (pintype "input"))
      (node (ref "E16") (pin "2") (pinfunction "J_2") (pintype "input"))
      (node (ref "E16") (pin "3") (pinfunction "K_3") (pintype "input"))
      (node (ref "E17") (pin "1") (pinfunction "CLK_1") (pintype "input"))
      (node (ref "E17") (pin "2") (pinfunction "PRE_2") (pintype "input"))
      (node (ref "E17") (pin "3") (pinfunction "CLR_3") (pintype "input"))
      (node (ref "E17") (pin "4") (pinfunction "J_4") (pintype "input"))
      (node (ref "E17") (pin "7") (pinfunction "PRE_7") (pintype "input"))
      (node (ref "E19") (pin "12") (pinfunction "D_12") (pintype "input"))
      (node (ref "E19") (pin "2") (pinfunction "D_2") (pintype "input"))
      (node (ref "E2") (pin "10") (pinfunction "PRE_10") (pintype "input"))
      (node (ref "E20") (pin "10") (pinfunction "I1_10") (pintype "input"))
      (node (ref "E20") (pin "9") (pinfunction "I0_9") (pintype "input"))
      (node (ref "E25") (pin "11") (pinfunction "I_11") (pintype "input"))
      (node (ref "E25") (pin "13") (pinfunction "I_13") (pintype "input"))
      (node (ref "E30") (pin "10") (pinfunction "PRE_10") (pintype "input"))
      (node (ref "E30") (pin "12") (pinfunction "D_12") (pintype "input"))
      (node (ref "E30") (pin "4") (pinfunction "PRE_4") (pintype "input"))
      (node (ref "E6") (pin "12") (pinfunction "D_12") (pintype "input"))
      (node (ref "E6") (pin "4") (pinfunction "PRE_4") (pintype "input"))
      (node (ref "R1") (pin "2") (pinfunction "2_2") (pintype "passive"))
      (node (ref "R18") (pin "2") (pinfunction "2_2") (pintype "passive"))
      (node (ref "R19") (pin "1") (pinfunction "1_1") (pintype "passive"))
      (node (ref "R2") (pin "2") (pinfunction "2_2") (pintype "passive"))
      (node (ref "R20") (pin "2") (pinfunction "2_2") (pintype "passive"))
      (node (ref "R3") (pin "2") (pinfunction "2_2") (pintype "passive"))
      (node (ref "R4") (pin "2") (pinfunction "2_2") (pintype "passive"))
      (node (ref "R5") (pin "2") (pinfunction "2_2") (pintype "passive"))
      (node (ref "R6") (pin "2") (pinfunction "2_2") (pintype "passive"))
      (node (ref "R7") (pin "2") (pinfunction "2_2") (pintype "passive"))
      (node (ref "R8") (pin "2") (pinfunction "2_2") (pintype "passive"))
      (node (ref "R9") (pin "2") (pinfunction "2_2") (pintype "passive"))
      (node (ref "SL1") (pin "1") (pinfunction "S_1") (pintype "passive"))
    )
    (net (code "156") (name "WRT") (class "Default")
      (node (ref "E10") (pin "5") (pinfunction "I2_5") (pintype "input"))
      (node (ref "E15") (pin "10") (pinfunction "I1_10") (pintype "input"))
      (node (ref "E25") (pin "2") (pinfunction "O_2") (pintype "output"))
      (node (ref "IC7") (pin "6") (pinfunction "I0_6") (pintype "input"))
    )
    (net (code "157") (name "XDR2") (class "Default")
      (node (ref "E10") (pin "2") (pinfunction "I1_2") (pintype "input"))
      (node (ref "E5") (pin "12") (pinfunction "I0_12") (pintype "input"))
      (node (ref "E5") (pin "8") (pinfunction "O_8") (pintype "output"))
    )
    (net (code "158") (name "XFER_REQ") (class "Default")
      (node (ref "E19") (pin "3") (pinfunction "CLK_3") (pintype "input"))
      (node (ref "E20") (pin "12") (pinfunction "I0_12") (pintype "input"))
      (node (ref "E36") (pin "4") (pinfunction "O_4") (pintype "output"))
    )
    (net (code "159") (name "unconnected-(D34L1-2-PadB)") (class "Default")
      (node (ref "D34L1") (pin "B") (pinfunction "2_B") (pintype "bidirectional"))
    )
    (net (code "160") (name "unconnected-(D34L1-34-PadNN)") (class "Default")
      (node (ref "D34L1") (pin "NN") (pinfunction "34_NN") (pintype "bidirectional"))
    )
    (net (code "161") (name "unconnected-(D34L1-38-PadTT)") (class "Default")
      (node (ref "D34L1") (pin "TT") (pinfunction "38_TT") (pintype "bidirectional"))
    )
    (net (code "162") (name "unconnected-(D34L1-40-PadVV)") (class "Default")
      (node (ref "D34L1") (pin "VV") (pinfunction "40_VV") (pintype "bidirectional"))
    )
    (net (code "163") (name "unconnected-(D34L2-2-PadB)") (class "Default")
      (node (ref "D34L2") (pin "B") (pinfunction "2_B") (pintype "bidirectional"))
    )
    (net (code "164") (name "unconnected-(D34L2-34-PadNN)") (class "Default")
      (node (ref "D34L2") (pin "NN") (pinfunction "34_NN") (pintype "bidirectional"))
    )
    (net (code "165") (name "unconnected-(D34L2-38-PadTT)") (class "Default")
      (node (ref "D34L2") (pin "TT") (pinfunction "38_TT") (pintype "bidirectional"))
    )
    (net (code "166") (name "unconnected-(D34L2-40-PadVV)") (class "Default")
      (node (ref "D34L2") (pin "VV") (pinfunction "40_VV") (pintype "bidirectional"))
    )
    (net (code "167") (name "unconnected-(D35L1-2-PadB)") (class "Default")
      (node (ref "D35L1") (pin "B") (pinfunction "2_B") (pintype "bidirectional"))
    )
    (net (code "168") (name "unconnected-(D35L1-40-PadVV)") (class "Default")
      (node (ref "D35L1") (pin "VV") (pinfunction "40_VV") (pintype "bidirectional"))
    )
    (net (code "169") (name "unconnected-(D35L2-2-PadB)") (class "Default")
      (node (ref "D35L2") (pin "B") (pinfunction "2_B") (pintype "bidirectional"))
    )
    (net (code "170") (name "unconnected-(D35L2-40-PadVV)") (class "Default")
      (node (ref "D35L2") (pin "VV") (pinfunction "40_VV") (pintype "bidirectional"))
    )
    (net (code "171") (name "unconnected-(D36L1-2-PadB)") (class "Default")
      (node (ref "D36L1") (pin "B") (pinfunction "2_B") (pintype "bidirectional"))
    )
    (net (code "172") (name "unconnected-(D36L1-40-PadVV)") (class "Default")
      (node (ref "D36L1") (pin "VV") (pinfunction "40_VV") (pintype "bidirectional"))
    )
    (net (code "173") (name "unconnected-(D36L2-2-PadB)") (class "Default")
      (node (ref "D36L2") (pin "B") (pinfunction "2_B") (pintype "bidirectional"))
    )
    (net (code "174") (name "unconnected-(D36L2-40-PadVV)") (class "Default")
      (node (ref "D36L2") (pin "VV") (pinfunction "40_VV") (pintype "bidirectional"))
    )
    (net (code "175") (name "unconnected-(E2A-Q-Pad5)") (class "Default")
      (node (ref "E2") (pin "5") (pinfunction "Q_5") (pintype "output"))
    )
    (net (code "176") (name "unconnected-(E4A-QA-Pad14)") (class "Default")
      (node (ref "E4") (pin "14") (pinfunction "QA_14") (pintype "output"))
    )
    (net (code "177") (name "unconnected-(E4A-QB-Pad13)") (class "Default")
      (node (ref "E4") (pin "13") (pinfunction "QB_13") (pintype "output"))
    )
    (net (code "178") (name "unconnected-(E4A-QC-Pad12)") (class "Default")
      (node (ref "E4") (pin "12") (pinfunction "QC_12") (pintype "output"))
    )
    (net (code "179") (name "unconnected-(E4A-QD-Pad11)") (class "Default")
      (node (ref "E4") (pin "11") (pinfunction "QD_11") (pintype "output"))
    )
    (net (code "180") (name "unconnected-(E6B-Q-Pad9)") (class "Default")
      (node (ref "E6") (pin "9") (pinfunction "Q_9") (pintype "output"))
    )
    (net (code "181") (name "unconnected-(E11A-Y0-Pad15)") (class "Default")
      (node (ref "E11") (pin "15") (pinfunction "Y0_15") (pintype "output"))
    )
    (net (code "182") (name "unconnected-(E11A-Y2-Pad13)") (class "Default")
      (node (ref "E11") (pin "13") (pinfunction "Y2_13") (pintype "output"))
    )
    (net (code "183") (name "unconnected-(E11A-Y3-Pad12)") (class "Default")
      (node (ref "E11") (pin "12") (pinfunction "Y3_12") (pintype "output"))
    )
    (net (code "184") (name "unconnected-(E11A-Y4-Pad11)") (class "Default")
      (node (ref "E11") (pin "11") (pinfunction "Y4_11") (pintype "output"))
    )
    (net (code "185") (name "unconnected-(E11A-Y5-Pad10)") (class "Default")
      (node (ref "E11") (pin "10") (pinfunction "Y5_10") (pintype "output"))
    )
    (net (code "186") (name "unconnected-(E11A-Y6-Pad9)") (class "Default")
      (node (ref "E11") (pin "9") (pinfunction "Y6_9") (pintype "output"))
    )
    (net (code "187") (name "unconnected-(E12A-Y0-Pad15)") (class "Default")
      (node (ref "E12") (pin "15") (pinfunction "Y0_15") (pintype "output"))
    )
    (net (code "188") (name "unconnected-(E12A-Y1-Pad14)") (class "Default")
      (node (ref "E12") (pin "14") (pinfunction "Y1_14") (pintype "output"))
    )
    (net (code "189") (name "unconnected-(E12A-Y4-Pad11)") (class "Default")
      (node (ref "E12") (pin "11") (pinfunction "Y4_11") (pintype "output"))
    )
    (net (code "190") (name "unconnected-(E12A-Y5-Pad10)") (class "Default")
      (node (ref "E12") (pin "10") (pinfunction "Y5_10") (pintype "output"))
    )
    (net (code "191") (name "unconnected-(E12A-Y6-Pad9)") (class "Default")
      (node (ref "E12") (pin "9") (pinfunction "Y6_9") (pintype "output"))
    )
    (net (code "192") (name "unconnected-(E12A-Y7-Pad7)") (class "Default")
      (node (ref "E12") (pin "7") (pinfunction "Y7_7") (pintype "output"))
    )
    (net (code "193") (name "unconnected-(E13A-Y0-Pad15)") (class "Default")
      (node (ref "E13") (pin "15") (pinfunction "Y0_15") (pintype "output"))
    )
    (net (code "194") (name "unconnected-(E13A-Y1-Pad14)") (class "Default")
      (node (ref "E13") (pin "14") (pinfunction "Y1_14") (pintype "output"))
    )
    (net (code "195") (name "unconnected-(E13A-Y2-Pad13)") (class "Default")
      (node (ref "E13") (pin "13") (pinfunction "Y2_13") (pintype "output"))
    )
    (net (code "196") (name "unconnected-(E13A-Y3-Pad12)") (class "Default")
      (node (ref "E13") (pin "12") (pinfunction "Y3_12") (pintype "output"))
    )
    (net (code "197") (name "unconnected-(E16A-QC-Pad13)") (class "Default")
      (node (ref "E16") (pin "13") (pinfunction "QC_13") (pintype "output"))
    )
    (net (code "198") (name "unconnected-(E17A-Q-Pad15)") (class "Default")
      (node (ref "E17") (pin "15") (pinfunction "Q_15") (pintype "output"))
    )
    (net (code "199") (name "unconnected-(E17A-~{Q}-Pad14)") (class "Default")
      (node (ref "E17") (pin "14") (pinfunction "~{Q}_14") (pintype "output"))
    )
    (net (code "200") (name "unconnected-(E17B-Q-Pad11)") (class "Default")
      (node (ref "E17") (pin "11") (pinfunction "Q_11") (pintype "output"))
    )
    (net (code "201") (name "unconnected-(E19A-Q-Pad5)") (class "Default")
      (node (ref "E19") (pin "5") (pinfunction "Q_5") (pintype "output"))
    )
    (net (code "202") (name "unconnected-(E19B-Q-Pad9)") (class "Default")
      (node (ref "E19") (pin "9") (pinfunction "Q_9") (pintype "output"))
    )
    (net (code "203") (name "unconnected-(E20C-O-Pad8)") (class "Default")
      (node (ref "E20") (pin "8") (pinfunction "O_8") (pintype "output"))
    )
    (net (code "204") (name "unconnected-(E21A-~{QD}-Pad11)") (class "Default")
      (node (ref "E21") (pin "11") (pinfunction "~{QD}_11") (pintype "output"))
    )
    (net (code "205") (name "unconnected-(E22A-~{QD}-Pad11)") (class "Default")
      (node (ref "E22") (pin "11") (pinfunction "~{QD}_11") (pintype "output"))
    )
    (net (code "206") (name "unconnected-(E23A-~{QD}-Pad11)") (class "Default")
      (node (ref "E23") (pin "11") (pinfunction "~{QD}_11") (pintype "output"))
    )
    (net (code "207") (name "unconnected-(E26D-O-Pad13)") (class "Default")
      (node (ref "E26") (pin "13") (pinfunction "O_13") (pintype "output"))
    )
    (net (code "208") (name "unconnected-(E30A-~{Q}-Pad6)") (class "Default")
      (node (ref "E30") (pin "6") (pinfunction "~{Q}_6") (pintype "output"))
    )
    (net (code "209") (name "unconnected-(E30B-~{Q}-Pad8)") (class "Default")
      (node (ref "E30") (pin "8") (pinfunction "~{Q}_8") (pintype "output"))
    )
    (net (code "210") (name "unconnected-(E36D-O-Pad13)") (class "Default")
      (node (ref "E36") (pin "13") (pinfunction "O_13") (pintype "output"))
    )
    (net (code "211") (name "unconnected-(LASTDEV-Pad8)") (class "Default")
      (node (ref "LASTDEV") (pin "8") (pinfunction "8_8") (pintype "passive"))
    )
    (net (code "212") (name "unconnected-(LASTDEV-Pad9)") (class "Default")
      (node (ref "LASTDEV") (pin "9") (pinfunction "9_9") (pintype "passive"))
    )
    (net (code "213") (name "unconnected-(LASTDEV-Pad10)") (class "Default")
      (node (ref "LASTDEV") (pin "10") (pinfunction "10_10") (pintype "passive"))
    )
    (net (code "214") (name "~{ACB00}") (class "Default")
      (node (ref "D34L1") (pin "D") (pinfunction "4_D") (pintype "bidirectional"))
      (node (ref "D34L2") (pin "D") (pinfunction "4_D") (pintype "bidirectional"))
      (node (ref "IC6") (pin "3") (pinfunction "O_3") (pintype "open_collector"))
    )
    (net (code "215") (name "~{ACB01}") (class "Default")
      (node (ref "D34L1") (pin "J") (pinfunction "8_J") (pintype "bidirectional"))
      (node (ref "D34L2") (pin "J") (pinfunction "8_J") (pintype "bidirectional"))
      (node (ref "IC6") (pin "5") (pinfunction "O_5") (pintype "open_collector"))
    )
    (net (code "216") (name "~{ACB02}") (class "Default")
      (node (ref "D34L1") (pin "N") (pinfunction "12_N") (pintype "bidirectional"))
      (node (ref "D34L2") (pin "N") (pinfunction "12_N") (pintype "bidirectional"))
      (node (ref "IC1") (pin "3") (pinfunction "O_3") (pintype "open_collector"))
    )
    (net (code "217") (name "~{ACB03}") (class "Default")
      (node (ref "D34L1") (pin "T") (pinfunction "16_T") (pintype "bidirectional"))
      (node (ref "D34L2") (pin "T") (pinfunction "16_T") (pintype "bidirectional"))
      (node (ref "IC2") (pin "5") (pinfunction "O_5") (pintype "open_collector"))
    )
    (net (code "218") (name "~{ACB04}") (class "Default")
      (node (ref "D34L1") (pin "X") (pinfunction "20_X") (pintype "bidirectional"))
      (node (ref "D34L2") (pin "X") (pinfunction "20_X") (pintype "bidirectional"))
      (node (ref "IC1") (pin "5") (pinfunction "O_5") (pintype "open_collector"))
    )
    (net (code "219") (name "~{ACB05}") (class "Default")
      (node (ref "D34L1") (pin "BB") (pinfunction "24_BB") (pintype "bidirectional"))
      (node (ref "D34L2") (pin "BB") (pinfunction "24_BB") (pintype "bidirectional"))
      (node (ref "IC4") (pin "3") (pinfunction "O_3") (pintype "open_collector"))
    )
    (net (code "220") (name "~{ACB06}") (class "Default")
      (node (ref "D34L1") (pin "FF") (pinfunction "28_FF") (pintype "bidirectional"))
      (node (ref "D34L2") (pin "FF") (pinfunction "28_FF") (pintype "bidirectional"))
      (node (ref "IC3") (pin "3") (pinfunction "O_3") (pintype "open_collector"))
    )
    (net (code "221") (name "~{ACB07}") (class "Default")
      (node (ref "D34L1") (pin "LL") (pinfunction "32_LL") (pintype "bidirectional"))
      (node (ref "D34L2") (pin "LL") (pinfunction "32_LL") (pintype "bidirectional"))
      (node (ref "IC3") (pin "5") (pinfunction "O_5") (pintype "open_collector"))
    )
    (net (code "222") (name "~{ACB08}") (class "Default")
      (node (ref "D34L1") (pin "RR") (pinfunction "36_RR") (pintype "bidirectional"))
      (node (ref "D34L2") (pin "RR") (pinfunction "36_RR") (pintype "bidirectional"))
      (node (ref "IC4") (pin "5") (pinfunction "O_5") (pintype "open_collector"))
    )
    (net (code "223") (name "~{ACB09}") (class "Default")
      (node (ref "D34L1") (pin "F") (pinfunction "6_F") (pintype "bidirectional"))
      (node (ref "D34L2") (pin "F") (pinfunction "6_F") (pintype "bidirectional"))
      (node (ref "IC5") (pin "3") (pinfunction "O_3") (pintype "open_collector"))
    )
    (net (code "224") (name "~{ACB10}") (class "Default")
      (node (ref "D34L1") (pin "L") (pinfunction "10_L") (pintype "bidirectional"))
      (node (ref "D34L2") (pin "L") (pinfunction "10_L") (pintype "bidirectional"))
      (node (ref "IC5") (pin "5") (pinfunction "O_5") (pintype "open_collector"))
    )
    (net (code "225") (name "~{ACB11}") (class "Default")
      (node (ref "D34L1") (pin "R") (pinfunction "14_R") (pintype "bidirectional"))
      (node (ref "D34L2") (pin "R") (pinfunction "14_R") (pintype "bidirectional"))
      (node (ref "IC2") (pin "3") (pinfunction "O_3") (pintype "open_collector"))
    )
    (net (code "226") (name "~{ACCLEAR}") (class "Default")
      (node (ref "D34L1") (pin "DD") (pinfunction "26_DD") (pintype "bidirectional"))
      (node (ref "D34L2") (pin "DD") (pinfunction "26_DD") (pintype "bidirectional"))
      (node (ref "IC7") (pin "3") (pinfunction "O_3") (pintype "open_collector"))
    )
    (net (code "227") (name "~{BMB03}") (class "Default")
      (node (ref "D35L1") (pin "T") (pinfunction "16_T") (pintype "bidirectional"))
      (node (ref "D35L2") (pin "T") (pinfunction "16_T") (pintype "bidirectional"))
    )
    (net (code "228") (name "~{BMB04}") (class "Default")
      (node (ref "D35L1") (pin "BB") (pinfunction "24_BB") (pintype "bidirectional"))
      (node (ref "D35L2") (pin "BB") (pinfunction "24_BB") (pintype "bidirectional"))
    )
    (net (code "229") (name "~{BMB05}") (class "Default")
      (node (ref "D35L1") (pin "LL") (pinfunction "32_LL") (pintype "bidirectional"))
      (node (ref "D35L2") (pin "LL") (pinfunction "32_LL") (pintype "bidirectional"))
    )
    (net (code "230") (name "~{BMB06}") (class "Default")
      (node (ref "D35L1") (pin "F") (pinfunction "6_F") (pintype "bidirectional"))
      (node (ref "D35L2") (pin "F") (pinfunction "6_F") (pintype "bidirectional"))
    )
    (net (code "231") (name "~{BMB07}") (class "Default")
      (node (ref "D35L1") (pin "R") (pinfunction "14_R") (pintype "bidirectional"))
      (node (ref "D35L2") (pin "R") (pinfunction "14_R") (pintype "bidirectional"))
    )
    (net (code "232") (name "~{BMB08}") (class "Default")
      (node (ref "D35L1") (pin "Z") (pinfunction "22_Z") (pintype "bidirectional"))
      (node (ref "D35L2") (pin "Z") (pinfunction "22_Z") (pintype "bidirectional"))
    )
    (net (code "233") (name "~{BRUN}") (class "Default")
      (node (ref "D34L1") (pin "JJ") (pinfunction "30_JJ") (pintype "bidirectional"))
      (node (ref "D34L2") (pin "JJ") (pinfunction "30_JJ") (pintype "bidirectional"))
    )
    (net (code "234") (name "~{CLK_PARITY}") (class "Default")
      (node (ref "E17") (pin "6") (pinfunction "CLK_6") (pintype "input"))
      (node (ref "E32") (pin "6") (pinfunction "O_6") (pintype "output"))
      (node (ref "E5") (pin "4") (pinfunction "I0_4") (pintype "input"))
      (node (ref "E5") (pin "5") (pinfunction "I1_5") (pintype "input"))
    )
    (net (code "235") (name "~{DONE_FF}") (class "Default")
      (node (ref "E16") (pin "12") (pinfunction "QD_12") (pintype "output"))
      (node (ref "E18") (pin "9") (pinfunction "I1_9") (pintype "input"))
    )
    (net (code "236") (name "~{DONE}") (class "Default")
      (node (ref "E10") (pin "4") (pinfunction "I1_4") (pintype "input"))
      (node (ref "E25") (pin "4") (pinfunction "O_4") (pintype "output"))
      (node (ref "E31") (pin "12") (pinfunction "I2_12") (pintype "input"))
    )
    (net (code "237") (name "~{ENB_BUF_LD}") (class "Default")
      (node (ref "E21") (pin "9") (pinfunction "S/~{L}_9") (pintype "input"))
      (node (ref "E22") (pin "9") (pinfunction "S/~{L}_9") (pintype "input"))
      (node (ref "E23") (pin "9") (pinfunction "S/~{L}_9") (pintype "input"))
      (node (ref "E24") (pin "11") (pinfunction "O_11") (pintype "output"))
      (node (ref "E32") (pin "13") (pinfunction "I2_13") (pintype "input"))
      (node (ref "E32") (pin "2") (pinfunction "I1_2") (pintype "input"))
      (node (ref "E4") (pin "9") (pinfunction "LD_9") (pintype "input"))
    )
    (net (code "238") (name "~{ERR_FF}") (class "Default")
      (node (ref "E16") (pin "14") (pinfunction "QB_14") (pintype "output"))
      (node (ref "E18") (pin "6") (pinfunction "I1_6") (pintype "input"))
    )
    (net (code "239") (name "~{INIT1}") (class "Default")
      (node (ref "E11") (pin "7") (pinfunction "Y7_7") (pintype "output"))
      (node (ref "E2") (pin "4") (pinfunction "PRE_4") (pintype "input"))
    )
    (net (code "240") (name "~{INIT4}") (class "Default")
      (node (ref "E13") (pin "7") (pinfunction "Y7_7") (pintype "output"))
      (node (ref "E2") (pin "3") (pinfunction "CLK_3") (pintype "input"))
    )
    (net (code "241") (name "~{INIT}") (class "Default")
      (node (ref "E15") (pin "6") (pinfunction "O_6") (pintype "output"))
      (node (ref "E16") (pin "1") (pinfunction "CLR_1") (pintype "input"))
      (node (ref "E2") (pin "13") (pinfunction "CLR_13") (pintype "input"))
      (node (ref "E21") (pin "1") (pinfunction "CLR_1") (pintype "input"))
      (node (ref "E22") (pin "1") (pinfunction "CLR_1") (pintype "input"))
      (node (ref "E23") (pin "1") (pinfunction "CLR_1") (pintype "input"))
      (node (ref "E24") (pin "9") (pinfunction "I0_9") (pintype "input"))
      (node (ref "E30") (pin "1") (pinfunction "CLR_1") (pintype "input"))
      (node (ref "E4") (pin "1") (pinfunction "CLR_1") (pintype "input"))
      (node (ref "E6") (pin "1") (pinfunction "CLR_1") (pintype "input"))
    )
    (net (code "242") (name "~{INTR4}") (class "Default")
      (node (ref "E13") (pin "9") (pinfunction "Y6_9") (pintype "output"))
      (node (ref "E30") (pin "3") (pinfunction "CLK_3") (pintype "input"))
    )
    (net (code "243") (name "~{INT_RQ}") (class "Default")
      (node (ref "D34L1") (pin "Z") (pinfunction "22_Z") (pintype "bidirectional"))
      (node (ref "D34L2") (pin "Z") (pinfunction "22_Z") (pintype "bidirectional"))
      (node (ref "IC10") (pin "5") (pinfunction "O_5") (pintype "open_collector"))
    )
    (net (code "244") (name "~{IOS}") (class "Default")
      (node (ref "D34L1") (pin "V") (pinfunction "18_V") (pintype "bidirectional"))
      (node (ref "D34L2") (pin "V") (pinfunction "18_V") (pintype "bidirectional"))
      (node (ref "IC10") (pin "3") (pinfunction "O_3") (pintype "open_collector"))
    )
    (net (code "245") (name "~{LCD1}") (class "Default")
      (node (ref "E10") (pin "9") (pinfunction "I0_9") (pintype "input"))
      (node (ref "E11") (pin "14") (pinfunction "Y1_14") (pintype "output"))
      (node (ref "E2") (pin "11") (pinfunction "CLK_11") (pintype "input"))
      (node (ref "E24") (pin "5") (pinfunction "I1_5") (pintype "input"))
      (node (ref "E25") (pin "5") (pinfunction "I_5") (pintype "input"))
      (node (ref "E6") (pin "3") (pinfunction "CLK_3") (pintype "input"))
    )
    (net (code "246") (name "~{MAINT}") (class "Default")
      (node (ref "E10") (pin "3") (pinfunction "I0_3") (pintype "input"))
      (node (ref "E19") (pin "10") (pinfunction "PRE_10") (pintype "input"))
      (node (ref "E19") (pin "4") (pinfunction "PRE_4") (pintype "input"))
      (node (ref "E24") (pin "13") (pinfunction "I1_13") (pintype "input"))
      (node (ref "E31") (pin "10") (pinfunction "I1_10") (pintype "input"))
      (node (ref "E31") (pin "5") (pinfunction "I3_5") (pintype "input"))
      (node (ref "E31") (pin "9") (pinfunction "I0_9") (pintype "input"))
      (node (ref "E6") (pin "10") (pinfunction "PRE_10") (pintype "input"))
      (node (ref "E6") (pin "6") (pinfunction "~{Q}_6") (pintype "output"))
    )
    (net (code "247") (name "~{MYDEV}") (class "Default")
      (node (ref "E11") (pin "4") (pinfunction "G2A_4") (pintype "input"))
      (node (ref "E12") (pin "4") (pinfunction "G2A_4") (pintype "input"))
      (node (ref "E13") (pin "4") (pinfunction "G2A_4") (pintype "input"))
      (node (ref "IOT") (pin "1") (pinfunction "P_1") (pintype "passive"))
    )
    (net (code "248") (name "~{PARITY}") (class "Default")
      (node (ref "E15") (pin "12") (pinfunction "I0_12") (pintype "input"))
      (node (ref "E17") (pin "10") (pinfunction "~{Q}_10") (pintype "output"))
    )
    (net (code "249") (name "~{RX_12_BIT}") (class "Default")
      (node (ref "DRIVE") (pin "FF") (pinfunction "28_FF") (pintype "bidirectional"))
      (node (ref "IC8") (pin "3") (pinfunction "O_3") (pintype "open_collector"))
      (node (ref "R16") (pin "2") (pinfunction "2_2") (pintype "passive"))
      (node (ref "R7") (pin "1") (pinfunction "1_1") (pintype "passive"))
    )
    (net (code "250") (name "~{RX_DATA}") (class "Default")
      (node (ref "DRIVE") (pin "BB") (pinfunction "24_BB") (pintype "bidirectional"))
      (node (ref "E35") (pin "2") (pinfunction "I0_2") (pintype "input"))
      (node (ref "IC7") (pin "5") (pinfunction "O_5") (pintype "open_collector"))
      (node (ref "R17") (pin "2") (pinfunction "2_2") (pintype "passive"))
      (node (ref "R8") (pin "1") (pinfunction "1_1") (pintype "passive"))
    )
    (net (code "251") (name "~{RX_DONE}") (class "Default")
      (node (ref "DRIVE") (pin "X") (pinfunction "20_X") (pintype "bidirectional"))
      (node (ref "E36") (pin "8") (pinfunction "I0_8") (pintype "input"))
      (node (ref "R13") (pin "2") (pinfunction "2_2") (pintype "passive"))
      (node (ref "R4") (pin "1") (pinfunction "1_1") (pintype "passive"))
    )
    (net (code "252") (name "~{RX_ERROR}") (class "Default")
      (node (ref "DRIVE") (pin "J") (pinfunction "8_J") (pintype "bidirectional"))
      (node (ref "E36") (pin "3") (pinfunction "I1_3") (pintype "input"))
      (node (ref "R14") (pin "2") (pinfunction "2_2") (pintype "passive"))
      (node (ref "R5") (pin "1") (pinfunction "1_1") (pintype "passive"))
    )
    (net (code "253") (name "~{RX_INIT}") (class "Default")
      (node (ref "DRIVE") (pin "N") (pinfunction "12_N") (pintype "bidirectional"))
      (node (ref "IC8") (pin "5") (pinfunction "O_5") (pintype "open_collector"))
      (node (ref "R20") (pin "1") (pinfunction "1_1") (pintype "passive"))
      (node (ref "R9") (pin "1") (pinfunction "1_1") (pintype "passive"))
    )
    (net (code "254") (name "~{RX_OUT}") (class "Default")
      (node (ref "DRIVE") (pin "RR") (pinfunction "36_RR") (pintype "bidirectional"))
      (node (ref "E35") (pin "8") (pinfunction "I0_8") (pintype "input"))
      (node (ref "R12") (pin "2") (pinfunction "2_2") (pintype "passive"))
      (node (ref "R3") (pin "1") (pinfunction "1_1") (pintype "passive"))
    )
    (net (code "255") (name "~{RX_RUN}") (class "Default")
      (node (ref "DRIVE") (pin "D") (pinfunction "4_D") (pintype "bidirectional"))
      (node (ref "IC9") (pin "5") (pinfunction "O_5") (pintype "open_collector"))
      (node (ref "R15") (pin "2") (pinfunction "2_2") (pintype "passive"))
      (node (ref "R6") (pin "1") (pinfunction "1_1") (pintype "passive"))
    )
    (net (code "256") (name "~{RX_SHIFT}") (class "Default")
      (node (ref "DRIVE") (pin "LL") (pinfunction "32_LL") (pintype "bidirectional"))
      (node (ref "E35") (pin "5") (pinfunction "I0_5") (pintype "input"))
      (node (ref "R10") (pin "2") (pinfunction "2_2") (pintype "passive"))
      (node (ref "R2") (pin "1") (pinfunction "1_1") (pintype "passive"))
    )
    (net (code "257") (name "~{RX_TR_REQ}") (class "Default")
      (node (ref "DRIVE") (pin "T") (pinfunction "16_T") (pintype "bidirectional"))
      (node (ref "E36") (pin "5") (pinfunction "I0_5") (pintype "input"))
      (node (ref "R1") (pin "1") (pinfunction "1_1") (pintype "passive"))
      (node (ref "R11") (pin "2") (pinfunction "2_2") (pintype "passive"))
    )
    (net (code "258") (name "~{SDN4}") (class "Default")
      (node (ref "E13") (pin "10") (pinfunction "Y5_10") (pintype "output"))
      (node (ref "E18") (pin "8") (pinfunction "I0_8") (pintype "input"))
    )
    (net (code "259") (name "~{SER4}") (class "Default")
      (node (ref "E13") (pin "11") (pinfunction "Y4_11") (pintype "output"))
      (node (ref "E18") (pin "5") (pinfunction "I0_5") (pintype "input"))
    )
    (net (code "260") (name "~{STR2}") (class "Default")
      (node (ref "E12") (pin "12") (pinfunction "Y3_12") (pintype "output"))
      (node (ref "E18") (pin "2") (pinfunction "I0_2") (pintype "input"))
    )
    (net (code "261") (name "~{TR_FF}") (class "Default")
      (node (ref "E16") (pin "15") (pinfunction "QA_15") (pintype "output"))
      (node (ref "E18") (pin "3") (pinfunction "I1_3") (pintype "input"))
    )
    (net (code "262") (name "~{XDR2}") (class "Default")
      (node (ref "E12") (pin "13") (pinfunction "Y2_13") (pintype "output"))
      (node (ref "E24") (pin "4") (pinfunction "I0_4") (pintype "input"))
      (node (ref "E25") (pin "9") (pinfunction "I_9") (pintype "input"))
      (node (ref "E35") (pin "12") (pinfunction "I1_12") (pintype "input"))
      (node (ref "E5") (pin "10") (pinfunction "I1_10") (pintype "input"))
      (node (ref "E5") (pin "9") (pinfunction "I0_9") (pintype "input"))
    )
  )
)
